# Fathom-Serial.net
KiCad netlist of a schematic drawn in EAGLE
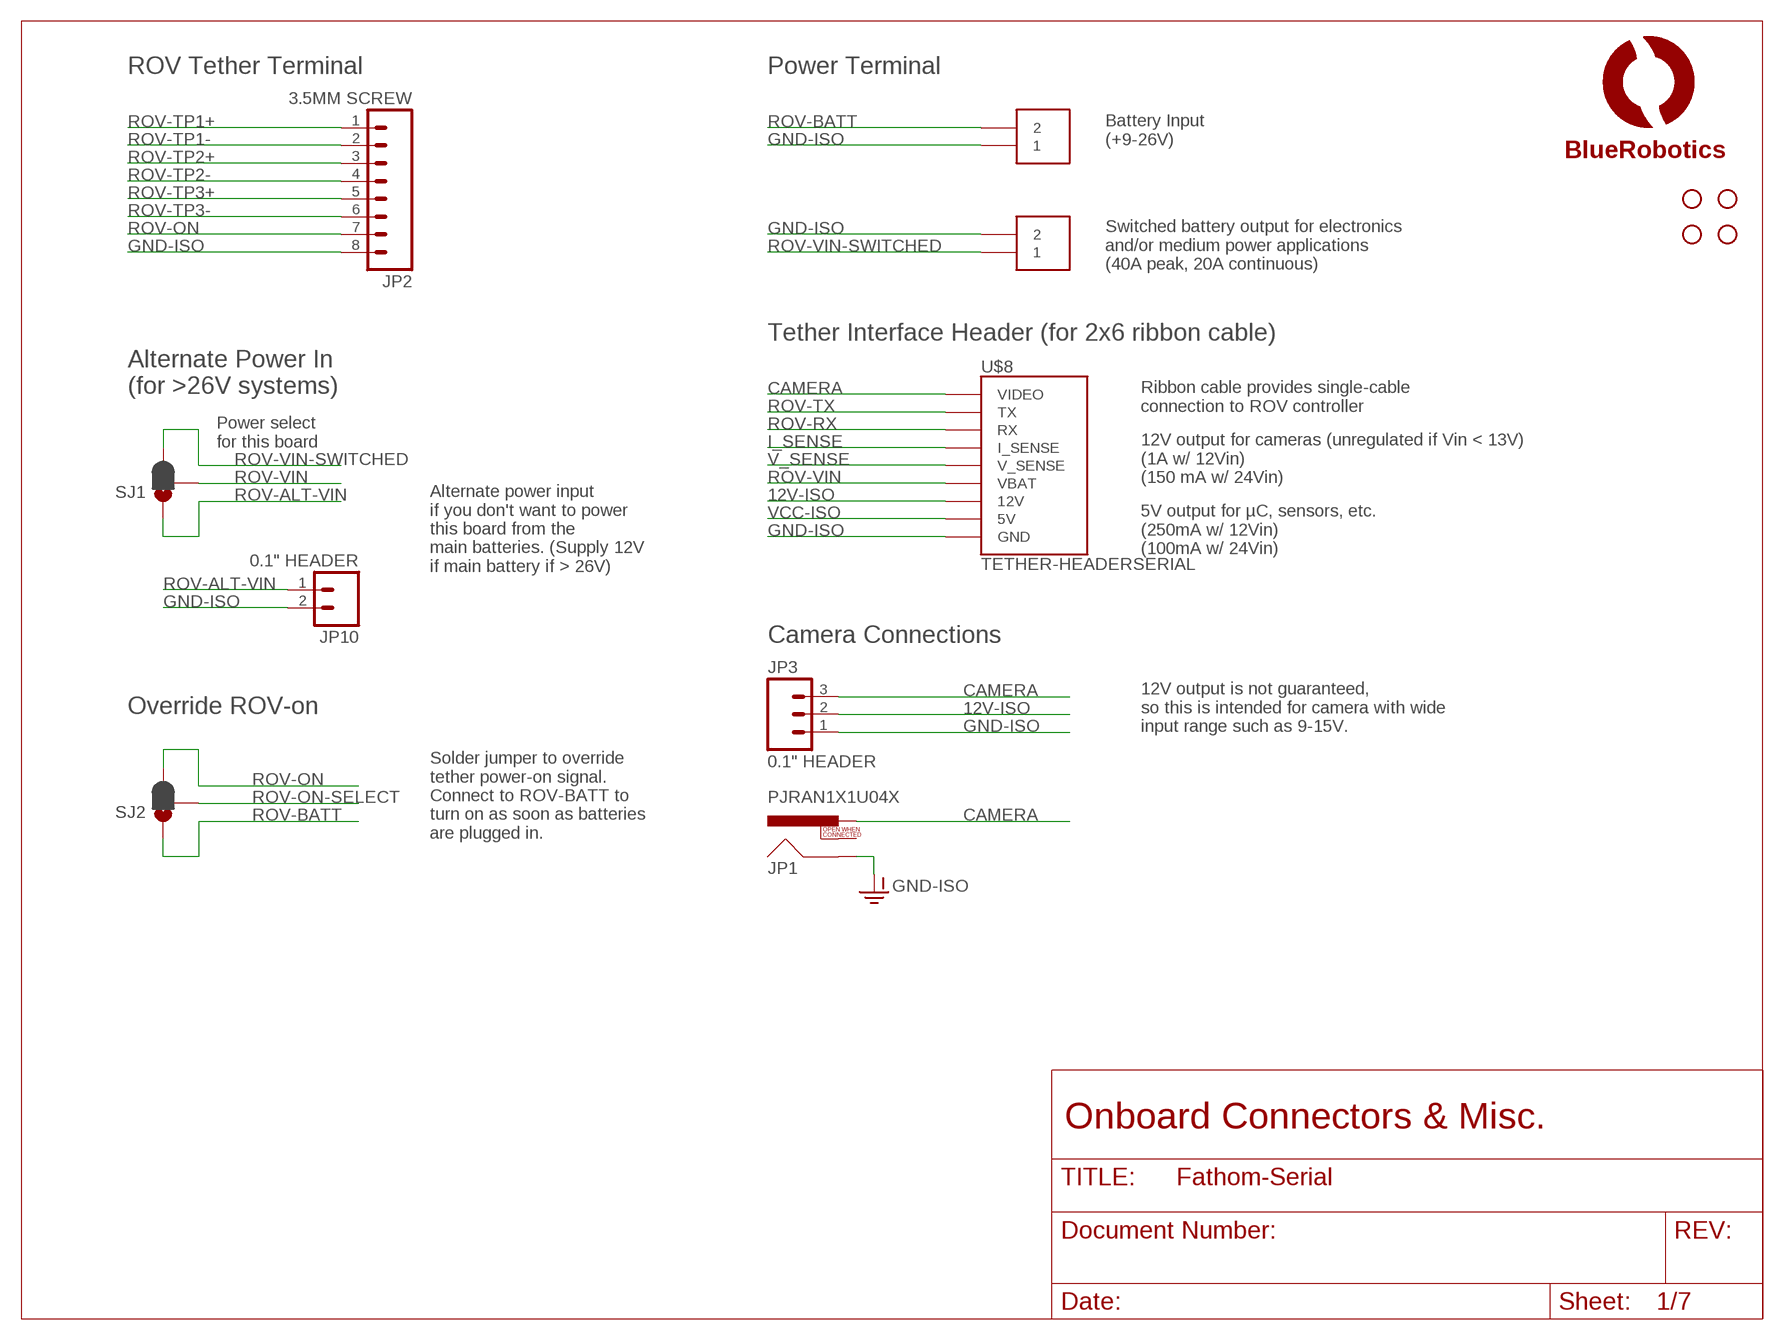
[diagram p0: schematic, sheet 1]
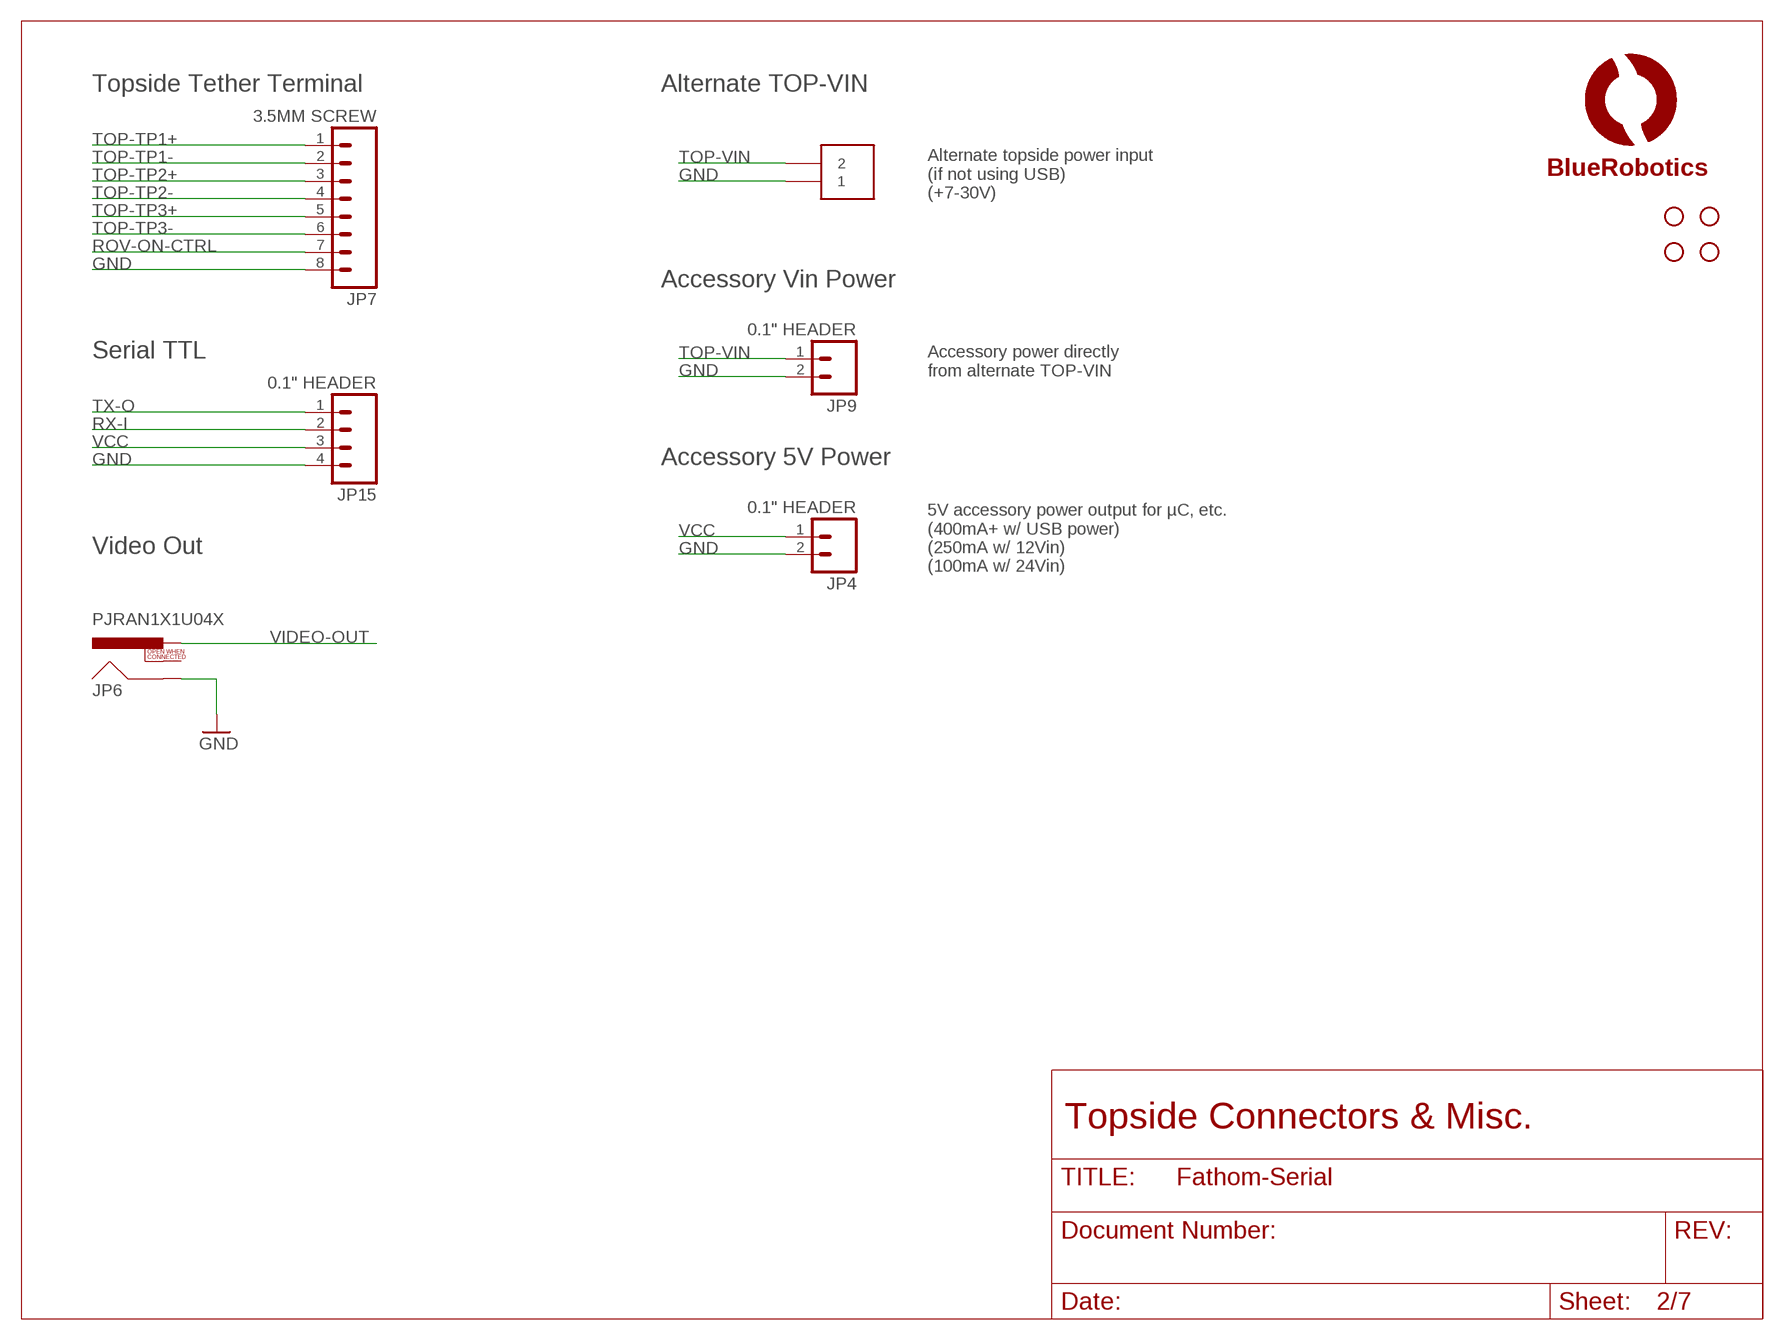
[diagram p1: schematic, sheet 2]
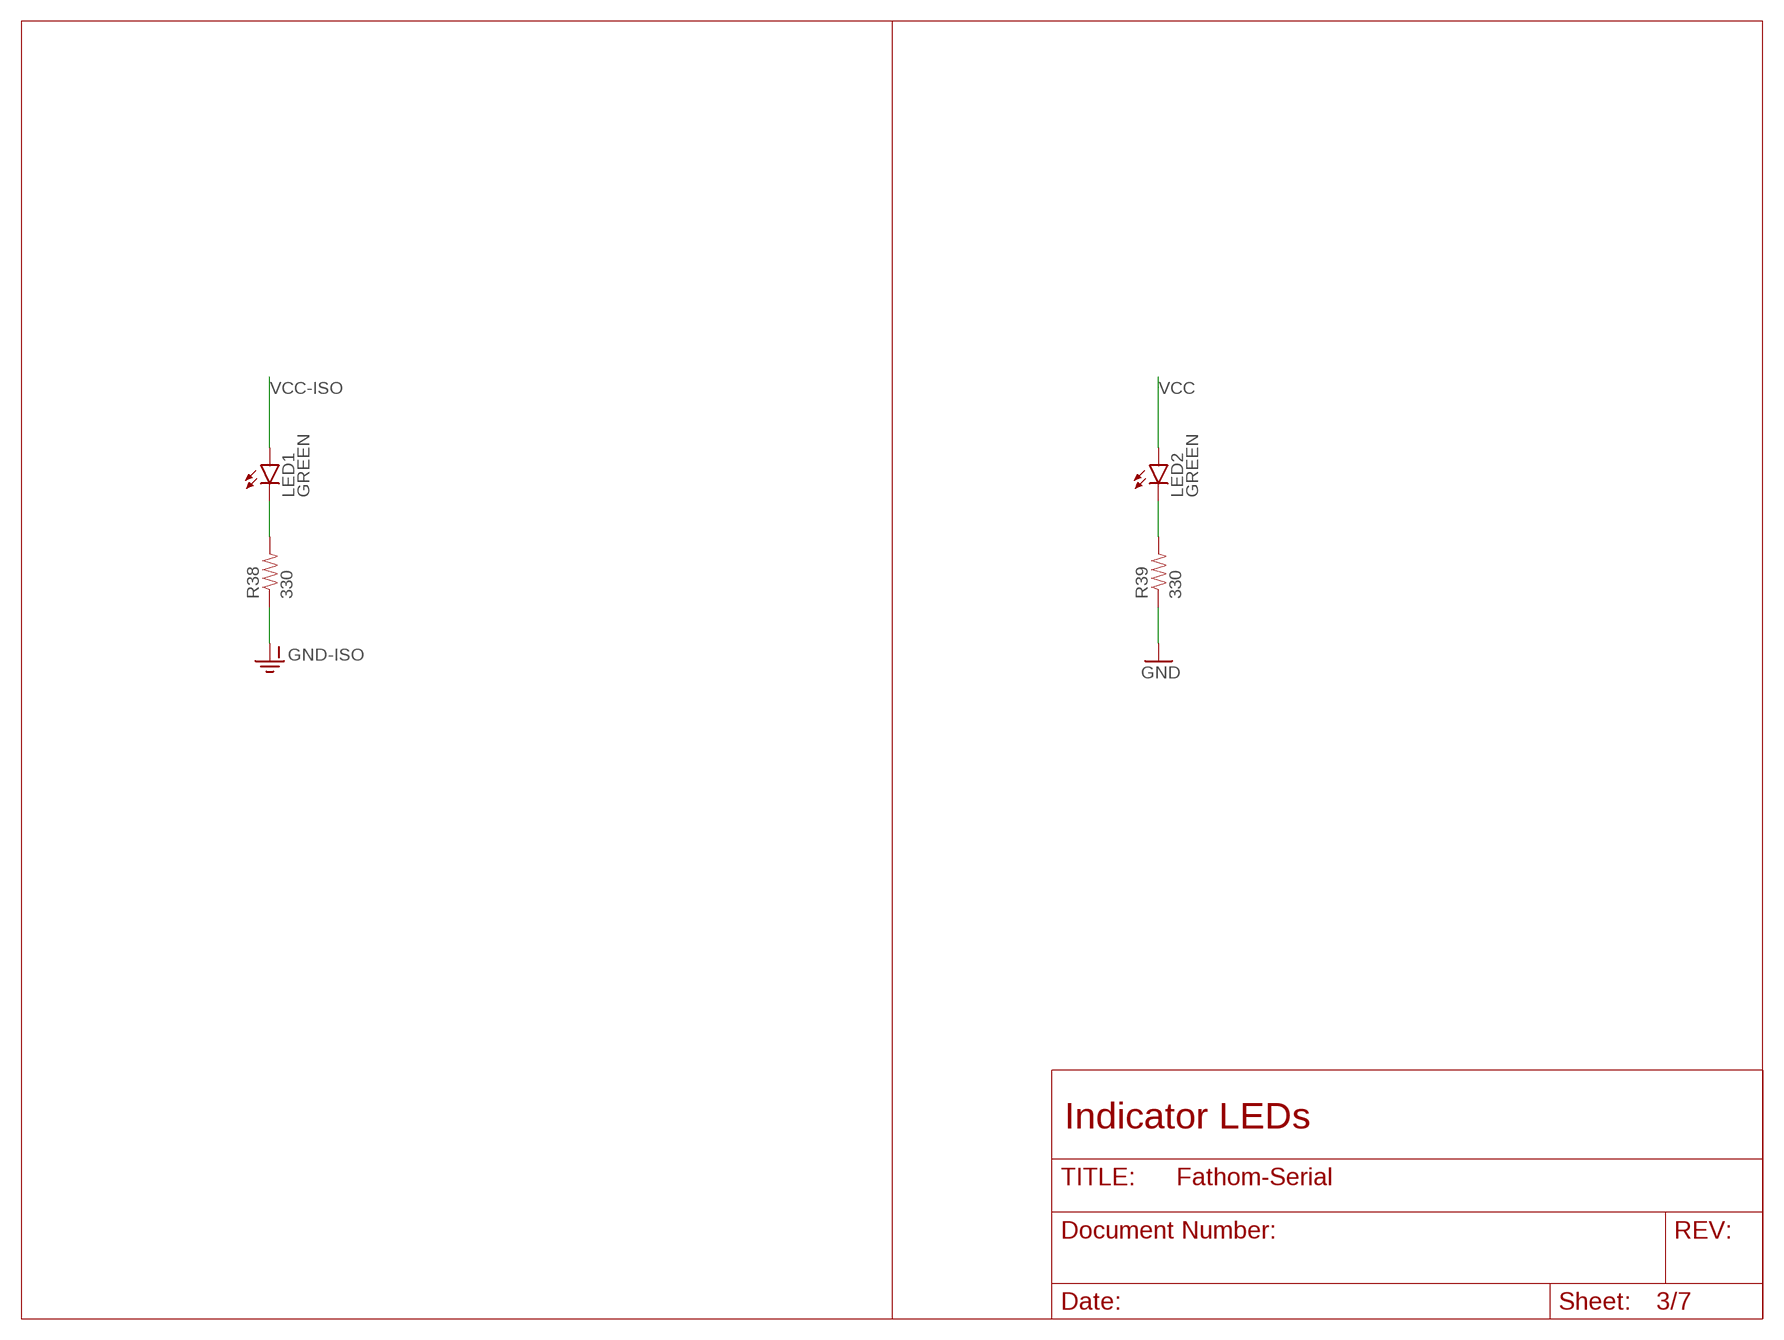
[diagram p2: schematic, sheet 3]
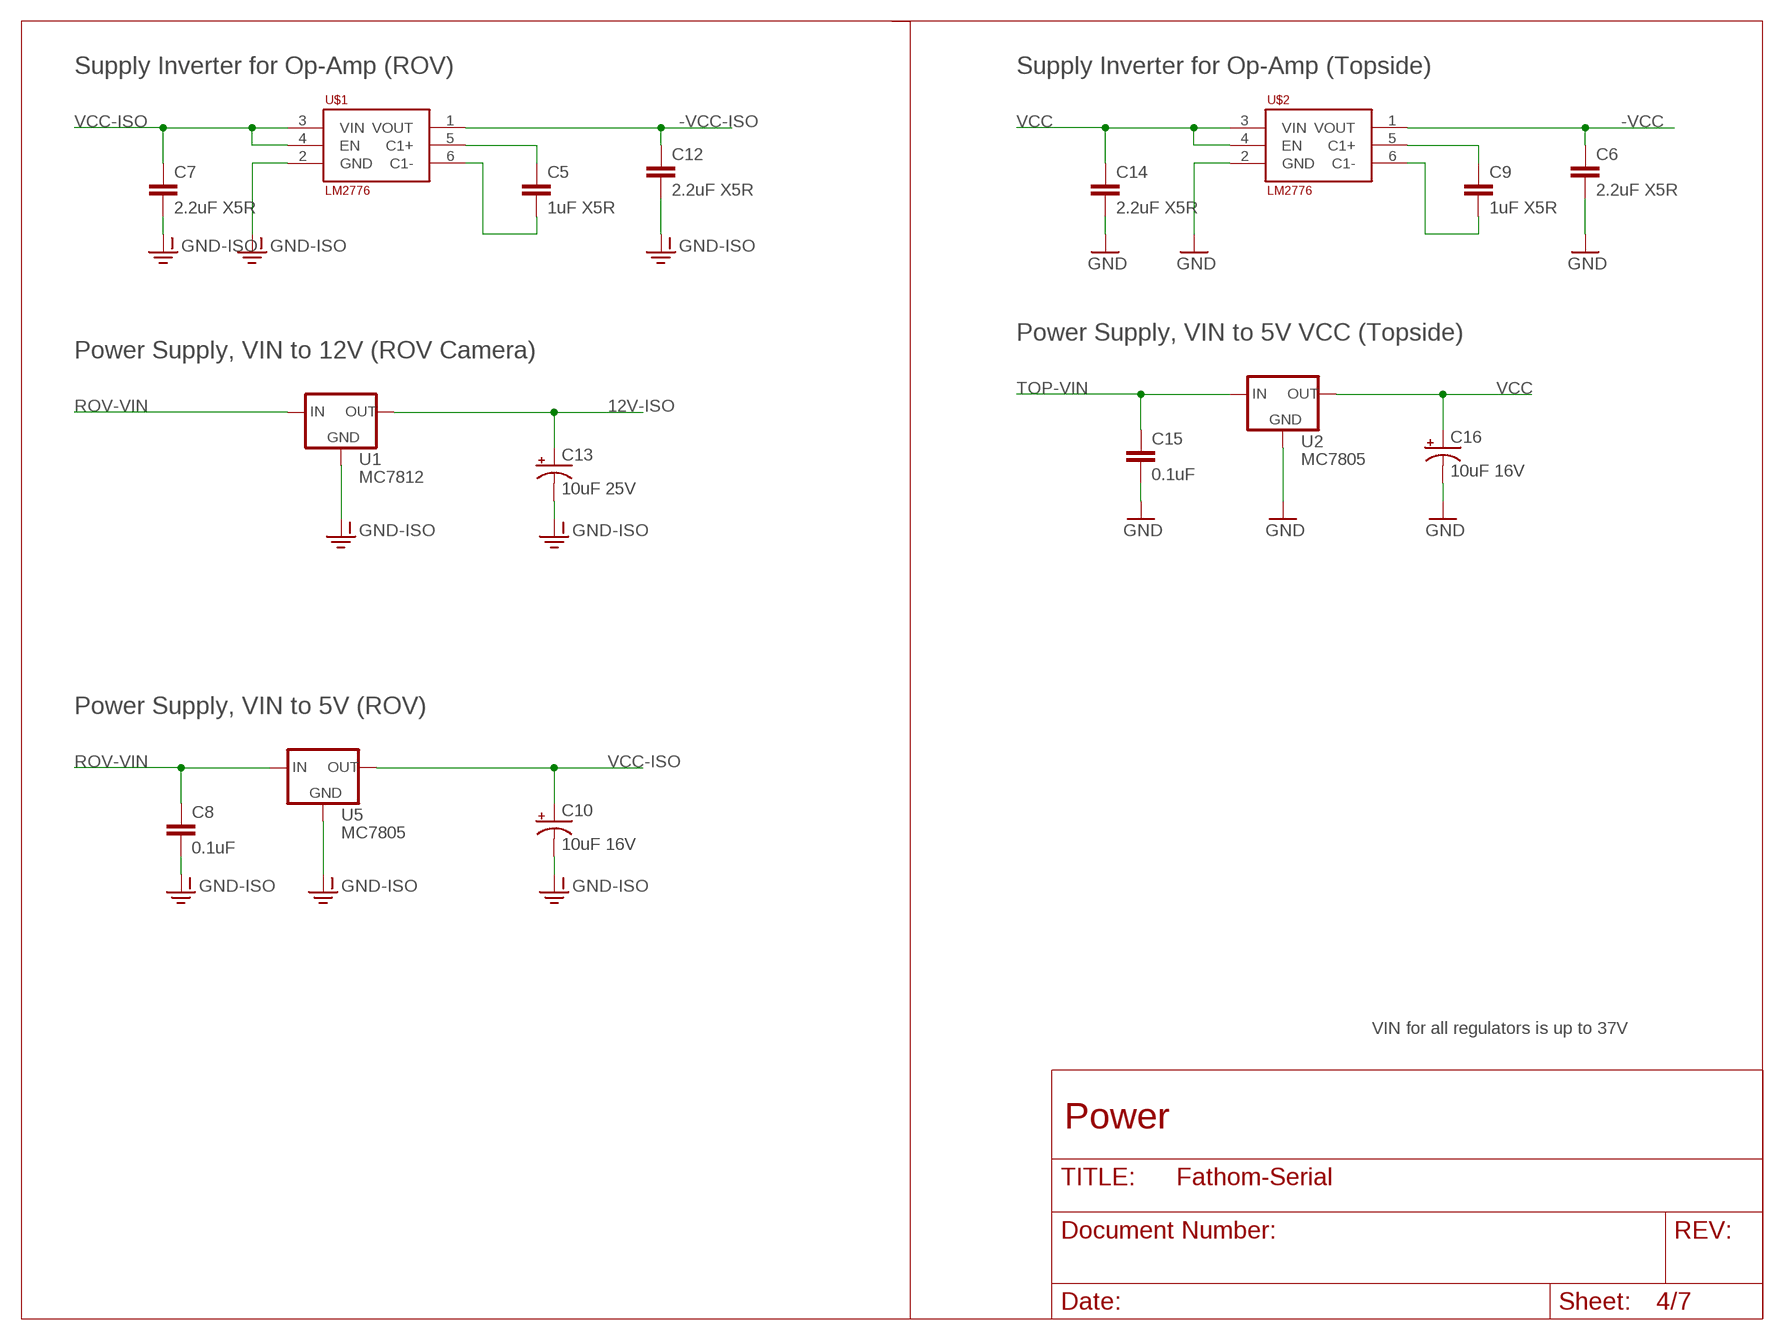
[diagram p3: schematic, sheet 4]
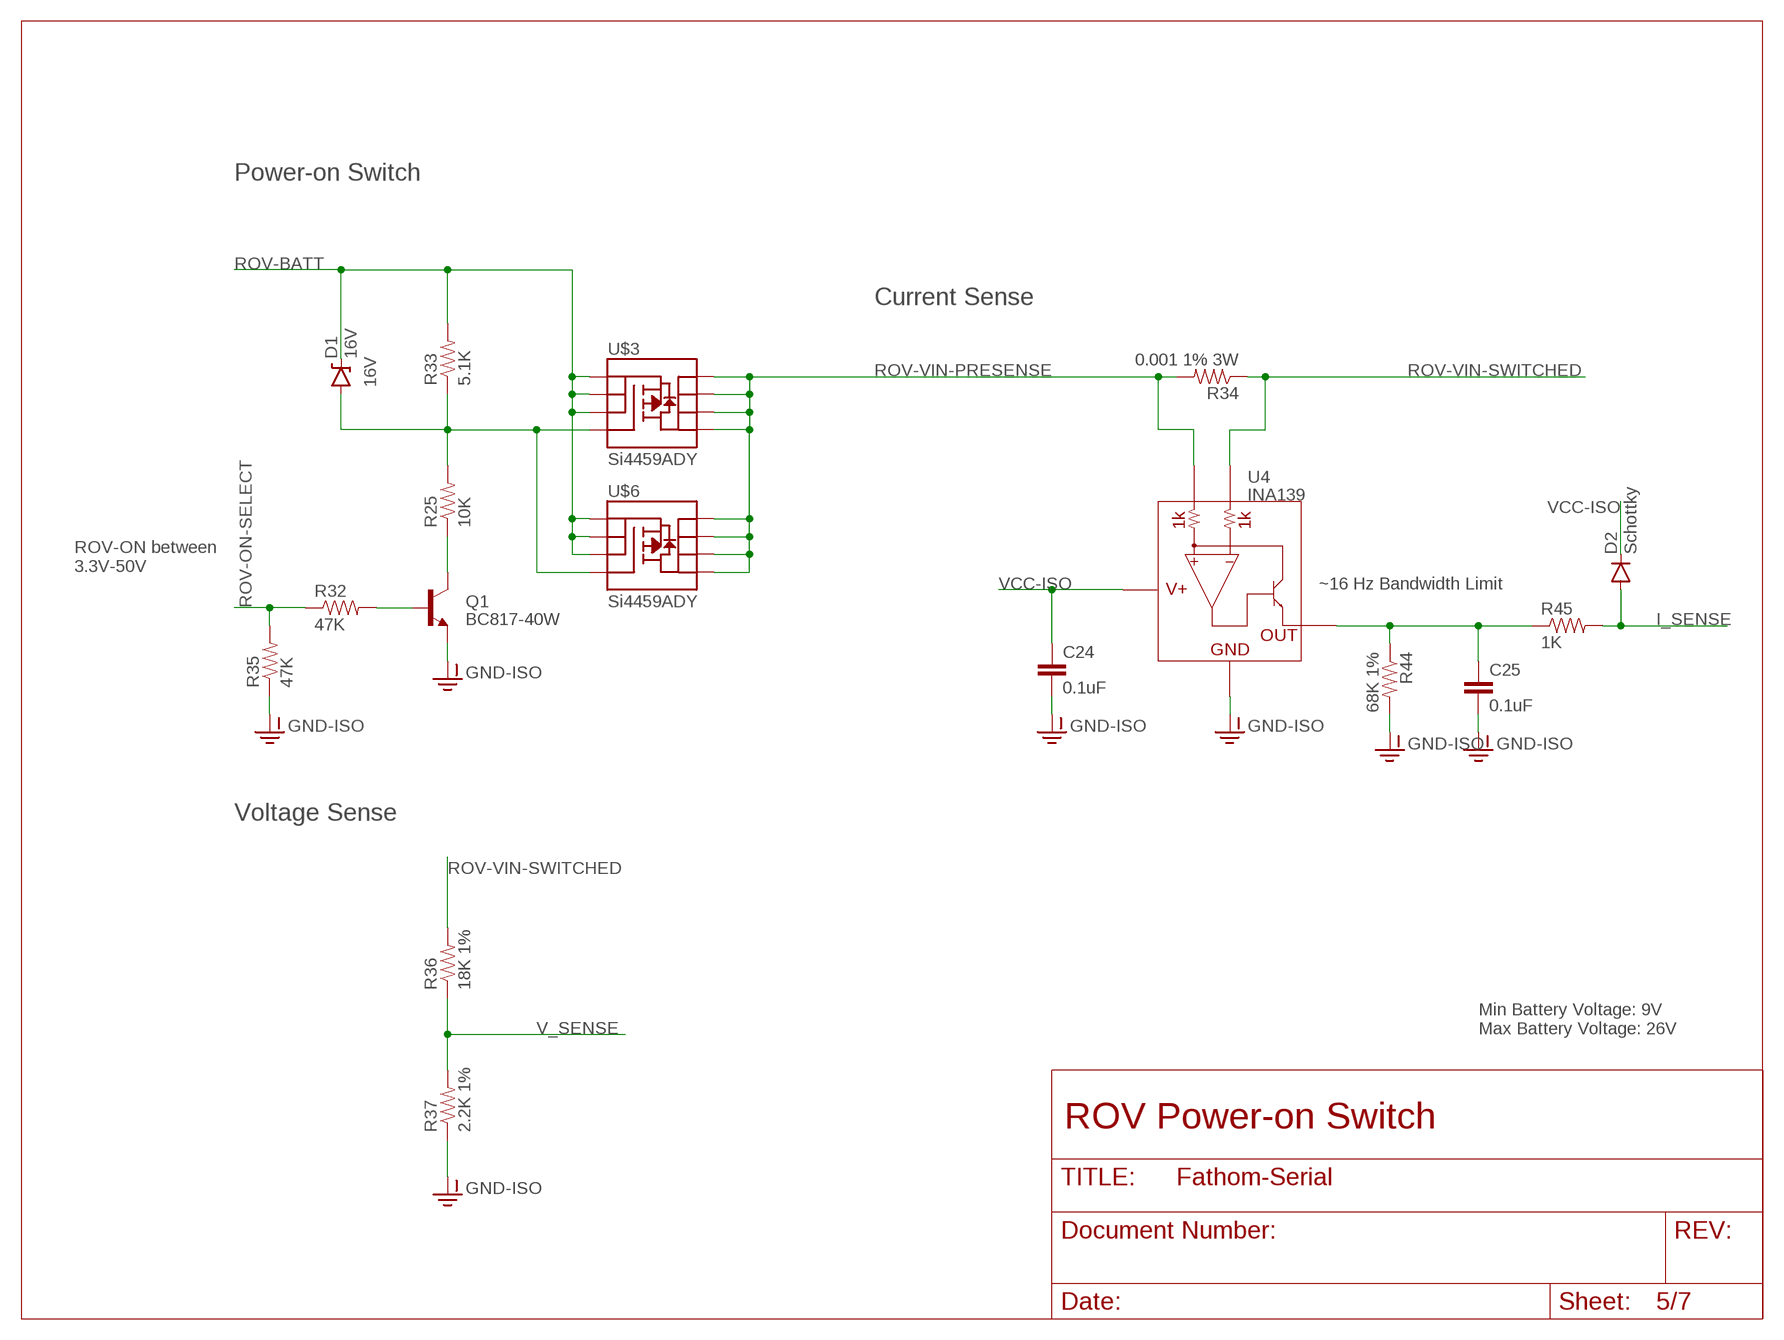
[diagram p4: schematic, sheet 5]
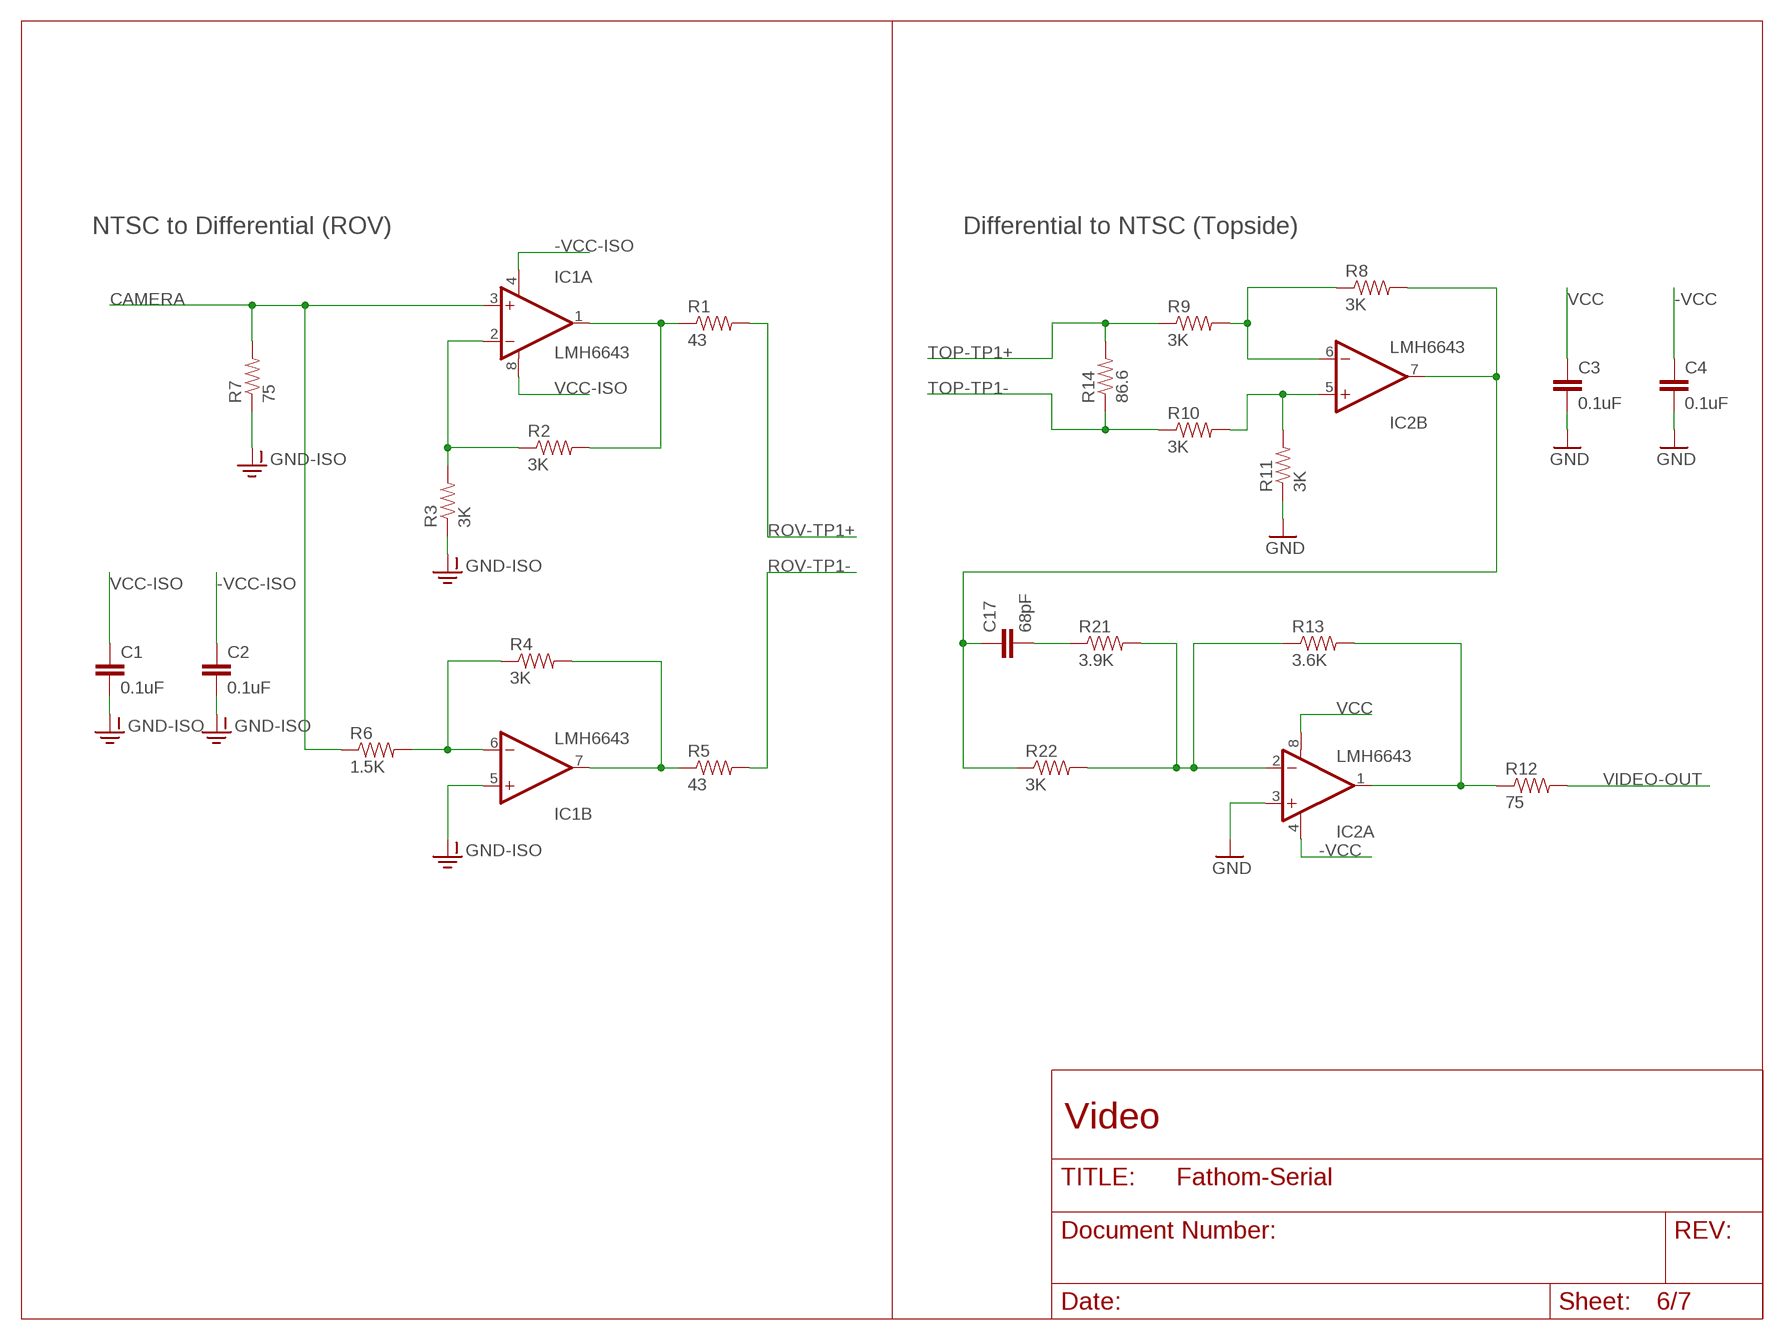
[diagram p5: schematic, sheet 6]
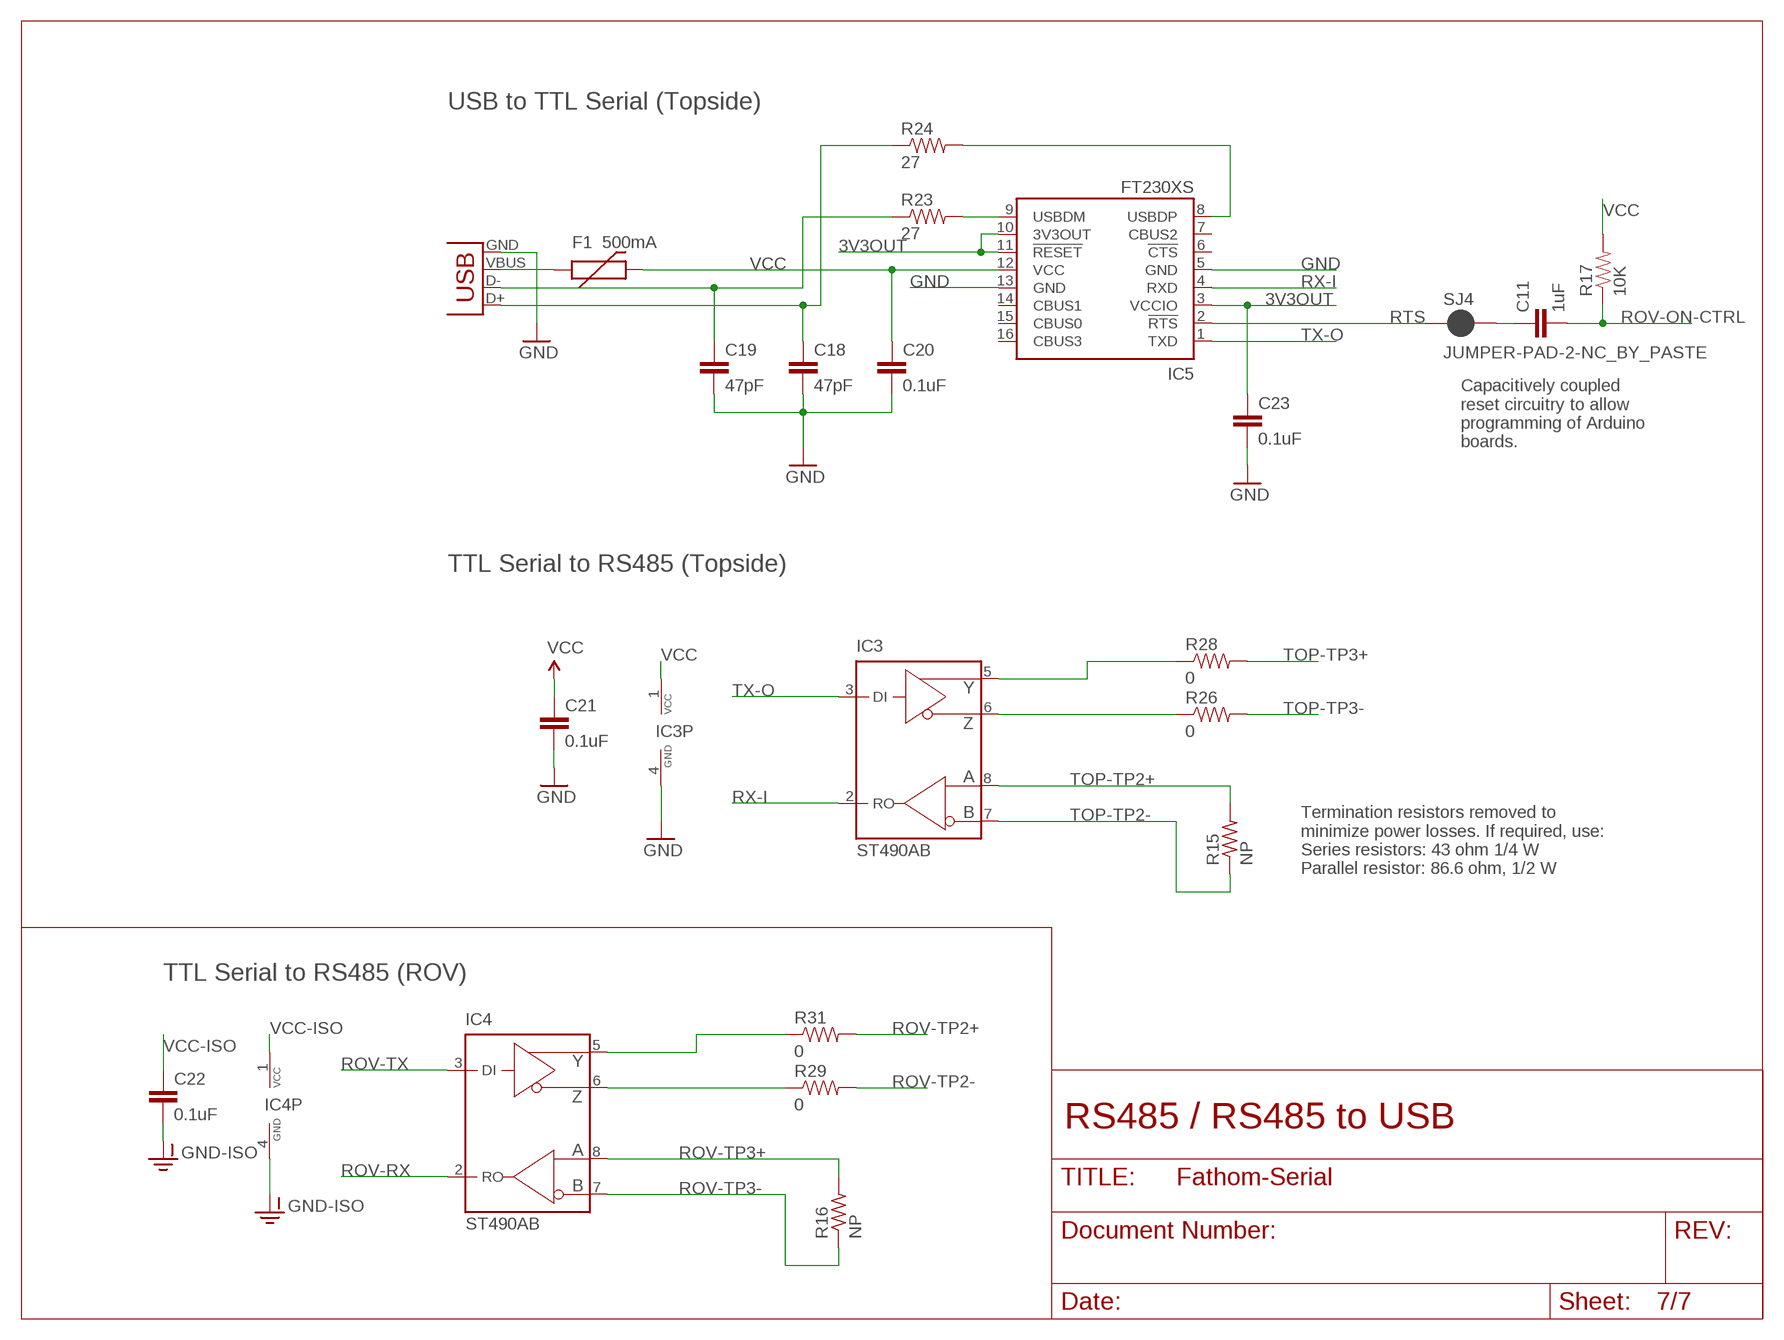
[diagram p6: schematic, sheet 7]

(export (version "E")
  (design (tool "Eeschema 10.0.6"))
  (components
    (comp (ref "JP1")
      (value "PJRAN1X1U04X")
      (footprint "eagle-import:RCA")
      (libsource (lib "eagle-import") (part "RCA"))
    )
    (comp (ref "JP2")
      (value "3.5MM SCREW")
      (footprint "eagle-import:SCREWTERMINAL-3.5MM-8")
      (libsource (lib "eagle-import") (part "M083.5MM-8"))
    )
    (comp (ref "JP3")
      (value "0.1\" HEADER")
      (footprint "eagle-import:1X03")
      (libsource (lib "eagle-import") (part "M03PTH"))
    )
    (comp (ref "JP10")
      (value "0.1\" HEADER")
      (footprint "eagle-import:1X02")
      (libsource (lib "eagle-import") (part "M02PTH"))
    )
    (comp (ref "SJ1")
      (value "JUMPER-PAD-3-2OF3_NC_BY_PASTE")
      (footprint "eagle-import:PAD-JUMPER-3-2OF3_NC_BY_PASTE_YES_SILK_FULL_BOX")
      (libsource (lib "eagle-import") (part "JUMPER-PAD-3-2OF3_NC_BY_PASTE"))
    )
    (comp (ref "SJ2")
      (value "JUMPER-PAD-3-2OF3_NC_BY_PASTE")
      (footprint "eagle-import:PAD-JUMPER-3-2OF3_NC_BY_PASTE_YES_SILK_FULL_BOX")
      (libsource (lib "eagle-import") (part "JUMPER-PAD-3-2OF3_NC_BY_PASTE"))
    )
    (comp (ref "STANDOFF1")
      (value "STAND-OFF")
      (footprint "eagle-import:STAND-OFF")
      (libsource (lib "eagle-import") (part "STAND-OFF"))
    )
    (comp (ref "STANDOFF2")
      (value "STAND-OFF")
      (footprint "eagle-import:STAND-OFF")
      (libsource (lib "eagle-import") (part "STAND-OFF"))
    )
    (comp (ref "STANDOFF3")
      (value "STAND-OFF")
      (footprint "eagle-import:STAND-OFF")
      (libsource (lib "eagle-import") (part "STAND-OFF"))
    )
    (comp (ref "STANDOFF4")
      (value "STAND-OFF")
      (footprint "eagle-import:STAND-OFF")
      (libsource (lib "eagle-import") (part "STAND-OFF"))
    )
    (comp (ref "U$4")
      (value "LOGOFULL-M")
      (footprint "eagle-import:BR-FULL-LOGO-MEDIUM")
      (libsource (lib "eagle-import") (part "LOGOFULL-M"))
    )
    (comp (ref "U$8")
      (value "TETHER-HEADERSERIAL")
      (footprint "eagle-import:TETHER-HEADER-2X7")
      (libsource (lib "eagle-import") (part "TETHER-HEADERSERIAL"))
    )
    (comp (ref "U$10")
      (value "HEADER-2")
      (footprint "eagle-import:TETHER-POWER-TERMINALS")
      (libsource (lib "eagle-import") (part "HEADER-2"))
    )
    (comp (ref "U$11")
      (value "HEADER-2")
      (footprint "eagle-import:TETHER-POWER-TERMINALS")
      (libsource (lib "eagle-import") (part "HEADER-2"))
    )
    (comp (ref "LED1")
      (value "GREEN")
      (footprint "eagle-import:LED-0603")
      (libsource (lib "eagle-import") (part "LED0603"))
    )
    (comp (ref "LED2")
      (value "GREEN")
      (footprint "eagle-import:LED-0603")
      (libsource (lib "eagle-import") (part "LED0603"))
    )
    (comp (ref "R38")
      (value "330")
      (footprint "eagle-import:0603-RES")
      (libsource (lib "eagle-import") (part "33KOHM1/10W1%(0603)"))
    )
    (comp (ref "R39")
      (value "330")
      (footprint "eagle-import:0603-RES")
      (libsource (lib "eagle-import") (part "33KOHM1/10W1%(0603)"))
    )
    (comp (ref "C11")
      (value "1uF")
      (footprint "eagle-import:0603-CAP")
      (libsource (lib "eagle-import") (part "CAP0603-CAP"))
    )
    (comp (ref "C18")
      (value "47pF")
      (footprint "eagle-import:0603-CAP")
      (libsource (lib "eagle-import") (part "CAP0603-CAP"))
    )
    (comp (ref "C19")
      (value "47pF")
      (footprint "eagle-import:0603-CAP")
      (libsource (lib "eagle-import") (part "CAP0603-CAP"))
    )
    (comp (ref "C20")
      (value "0.1uF")
      (footprint "eagle-import:0603-CAP")
      (libsource (lib "eagle-import") (part "CAP0603-CAP"))
    )
    (comp (ref "C21")
      (value "0.1uF")
      (footprint "eagle-import:0603-CAP")
      (libsource (lib "eagle-import") (part "CAP0603-CAP"))
    )
    (comp (ref "C22")
      (value "0.1uF")
      (footprint "eagle-import:0603-CAP")
      (libsource (lib "eagle-import") (part "CAP0603-CAP"))
    )
    (comp (ref "C23")
      (value "0.1uF")
      (footprint "eagle-import:0603-CAP")
      (libsource (lib "eagle-import") (part "CAP0603-CAP"))
    )
    (comp (ref "F1")
      (value "500mA")
      (footprint "eagle-import:0603")
      (libsource (lib "eagle-import") (part "PTC0603"))
    )
    (comp (ref "IC3")
      (value "ST490AB")
      (footprint "eagle-import:SO08")
      (fields (field (name "MF") "MAXIM") (field (name "MPN") "MAX488CSA"))
      (libsource (lib "eagle-import") (part "MAX488CSA"))
    )
    (comp (ref "IC4")
      (value "ST490AB")
      (footprint "eagle-import:SO08")
      (fields (field (name "MF") "MAXIM") (field (name "MPN") "MAX488CSA"))
      (libsource (lib "eagle-import") (part "MAX488CSA"))
    )
    (comp (ref "IC5")
      (value "FT230XS")
      (footprint "eagle-import:SSOP16")
      (libsource (lib "eagle-import") (part "FT230XS"))
    )
    (comp (ref "R15")
      (value "NP")
      (footprint "eagle-import:R1210")
      (libsource (lib "eagle-import") (part "R-US_R1210"))
    )
    (comp (ref "R16")
      (value "NP")
      (footprint "eagle-import:R1210")
      (libsource (lib "eagle-import") (part "R-US_R1210"))
    )
    (comp (ref "R17")
      (value "10K")
      (footprint "eagle-import:0603-RES")
      (libsource (lib "eagle-import") (part "RESISTOR0603-RES"))
    )
    (comp (ref "R23")
      (value "27")
      (footprint "eagle-import:0603-RES")
      (libsource (lib "eagle-import") (part "RESISTOR0603-RES"))
    )
    (comp (ref "R24")
      (value "27")
      (footprint "eagle-import:0603-RES")
      (libsource (lib "eagle-import") (part "RESISTOR0603-RES"))
    )
    (comp (ref "R26")
      (value "0")
      (footprint "eagle-import:1206")
      (libsource (lib "eagle-import") (part "RESISTOR1206"))
    )
    (comp (ref "R28")
      (value "0")
      (footprint "eagle-import:1206")
      (libsource (lib "eagle-import") (part "RESISTOR1206"))
    )
    (comp (ref "R29")
      (value "0")
      (footprint "eagle-import:1206")
      (libsource (lib "eagle-import") (part "RESISTOR1206"))
    )
    (comp (ref "R31")
      (value "0")
      (footprint "eagle-import:1206")
      (libsource (lib "eagle-import") (part "RESISTOR1206"))
    )
    (comp (ref "SJ4")
      (value "JUMPER-PAD-2-NC_BY_PASTE")
      (footprint "eagle-import:PAD-JUMPER-2-NC_BY_PASTE_YES_SILK")
      (libsource (lib "eagle-import") (part "JUMPER-PAD-2-NC_BY_PASTE"))
    )
    (comp (ref "X2")
      (value "USBSMD")
      (footprint "eagle-import:USB-MINIB")
      (libsource (lib "eagle-import") (part "USBSMD"))
    )
    (comp (ref "C24")
      (value "0.1uF")
      (footprint "eagle-import:0603-CAP")
      (libsource (lib "eagle-import") (part "SparkFun-Passives_CAP0603-CAP"))
    )
    (comp (ref "C25")
      (value "0.1uF")
      (footprint "eagle-import:0603-CAP")
      (libsource (lib "eagle-import") (part "SparkFun-Passives_CAP0603-CAP"))
    )
    (comp (ref "D1")
      (value "16V")
      (footprint "eagle-import:SOD-323")
      (libsource (lib "eagle-import") (part "DIODE-ZENER3.3V"))
    )
    (comp (ref "D2")
      (value "Schottky")
      (footprint "eagle-import:SOD-323")
      (libsource (lib "eagle-import") (part "DIODESOD"))
    )
    (comp (ref "Q1")
      (value "BC817-40W")
      (footprint "eagle-import:SOT23")
      (libsource (lib "eagle-import") (part "TRANSISTOR_NPNSOT23"))
    )
    (comp (ref "R25")
      (value "10K")
      (footprint "eagle-import:0603-RES")
      (libsource (lib "eagle-import") (part "33KOHM1/10W1%(0603)"))
    )
    (comp (ref "R32")
      (value "47K")
      (footprint "eagle-import:0603-RES")
      (libsource (lib "eagle-import") (part "33KOHM1/10W1%(0603)"))
    )
    (comp (ref "R33")
      (value "5.1K")
      (footprint "eagle-import:0603-RES")
      (libsource (lib "eagle-import") (part "33KOHM1/10W1%(0603)"))
    )
    (comp (ref "R34")
      (value "0.001 1% 3W")
      (footprint "eagle-import:R2512")
      (libsource (lib "eagle-import") (part "SparkFun-Resistors_RESISTOR2512"))
    )
    (comp (ref "R35")
      (value "47K")
      (footprint "eagle-import:0603-RES")
      (libsource (lib "eagle-import") (part "33KOHM1/10W1%(0603)"))
    )
    (comp (ref "R36")
      (value "18K 1%")
      (footprint "eagle-import:0603-RES")
      (libsource (lib "eagle-import") (part "33KOHM1/10W1%(0603)"))
    )
    (comp (ref "R37")
      (value "2.2K 1%")
      (footprint "eagle-import:0603-RES")
      (libsource (lib "eagle-import") (part "33KOHM1/10W1%(0603)"))
    )
    (comp (ref "R44")
      (value "68K 1%")
      (footprint "eagle-import:0603-RES")
      (libsource (lib "eagle-import") (part "33KOHM1/10W1%(0603)"))
    )
    (comp (ref "R45")
      (value "1K")
      (footprint "eagle-import:0603-RES")
      (libsource (lib "eagle-import") (part "33KOHM1/10W1%(0603)"))
    )
    (comp (ref "U$3")
      (value "Si4459ADY")
      (footprint "eagle-import:SO08")
      (libsource (lib "eagle-import") (part "MOSFET-PCHANNEL-SOIC8SOIC8"))
    )
    (comp (ref "U$6")
      (value "Si4459ADY")
      (footprint "eagle-import:SO08")
      (libsource (lib "eagle-import") (part "MOSFET-PCHANNEL-SOIC8SOIC8"))
    )
    (comp (ref "U4")
      (value "INA139")
      (footprint "eagle-import:SOT23-5")
      (libsource (lib "eagle-import") (part "INA139"))
    )
    (comp (ref "C5")
      (value "1uF X5R")
      (footprint "eagle-import:0603-CAP")
      (libsource (lib "eagle-import") (part "SparkFun-Passives_CAP0603-CAP"))
    )
    (comp (ref "C6")
      (value "2.2uF X5R")
      (footprint "eagle-import:0603-CAP")
      (libsource (lib "eagle-import") (part "SparkFun-Passives_CAP0603-CAP"))
    )
    (comp (ref "C7")
      (value "2.2uF X5R")
      (footprint "eagle-import:0603-CAP")
      (libsource (lib "eagle-import") (part "SparkFun-Passives_CAP0603-CAP"))
    )
    (comp (ref "C8")
      (value "0.1uF")
      (footprint "eagle-import:0603-CAP")
      (libsource (lib "eagle-import") (part "SparkFun-Passives_CAP0603-CAP"))
    )
    (comp (ref "C9")
      (value "1uF X5R")
      (footprint "eagle-import:0603-CAP")
      (libsource (lib "eagle-import") (part "SparkFun-Passives_CAP0603-CAP"))
    )
    (comp (ref "C10")
      (value "10uF 16V")
      (footprint "eagle-import:EIA3216")
      (libsource (lib "eagle-import") (part "CAP_POL1206"))
    )
    (comp (ref "C12")
      (value "2.2uF X5R")
      (footprint "eagle-import:0603-CAP")
      (libsource (lib "eagle-import") (part "SparkFun-Passives_CAP0603-CAP"))
    )
    (comp (ref "C13")
      (value "10uF 25V")
      (footprint "eagle-import:EIA6032")
      (libsource (lib "eagle-import") (part "CAP_POL6032"))
    )
    (comp (ref "C14")
      (value "2.2uF X5R")
      (footprint "eagle-import:0603-CAP")
      (libsource (lib "eagle-import") (part "SparkFun-Passives_CAP0603-CAP"))
    )
    (comp (ref "C15")
      (value "0.1uF")
      (footprint "eagle-import:0603-CAP")
      (libsource (lib "eagle-import") (part "SparkFun-Passives_CAP0603-CAP"))
    )
    (comp (ref "C16")
      (value "10uF 16V")
      (footprint "eagle-import:EIA3216")
      (libsource (lib "eagle-import") (part "CAP_POL1206"))
    )
    (comp (ref "U$1")
      (value "LM2776")
      (footprint "eagle-import:SOT-23-6")
      (libsource (lib "eagle-import") (part "LM2776"))
    )
    (comp (ref "U$2")
      (value "LM2776")
      (footprint "eagle-import:SOT-23-6")
      (libsource (lib "eagle-import") (part "LM2776"))
    )
    (comp (ref "U1")
      (value "MC7812")
      (footprint "eagle-import:DPAK")
      (libsource (lib "eagle-import") (part "78XX"))
    )
    (comp (ref "U2")
      (value "MC7805")
      (footprint "eagle-import:DPAK")
      (libsource (lib "eagle-import") (part "78XX"))
    )
    (comp (ref "U5")
      (value "MC7805")
      (footprint "eagle-import:DPAK")
      (libsource (lib "eagle-import") (part "78XX"))
    )
    (comp (ref "JP4")
      (value "0.1\" HEADER")
      (footprint "eagle-import:1X02")
      (libsource (lib "eagle-import") (part "M02PTH"))
    )
    (comp (ref "JP6")
      (value "PJRAN1X1U04X")
      (footprint "eagle-import:RCA")
      (libsource (lib "eagle-import") (part "RCA"))
    )
    (comp (ref "JP7")
      (value "3.5MM SCREW")
      (footprint "eagle-import:SCREWTERMINAL-3.5MM-8")
      (libsource (lib "eagle-import") (part "M083.5MM-8"))
    )
    (comp (ref "JP9")
      (value "0.1\" HEADER")
      (footprint "eagle-import:1X02")
      (libsource (lib "eagle-import") (part "M02PTH"))
    )
    (comp (ref "JP15")
      (value "0.1\" HEADER")
      (footprint "eagle-import:1X04")
      (libsource (lib "eagle-import") (part "M04PTH"))
    )
    (comp (ref "STANDOFF5")
      (value "STAND-OFF")
      (footprint "eagle-import:STAND-OFF")
      (libsource (lib "eagle-import") (part "STAND-OFF"))
    )
    (comp (ref "STANDOFF6")
      (value "STAND-OFF")
      (footprint "eagle-import:STAND-OFF")
      (libsource (lib "eagle-import") (part "STAND-OFF"))
    )
    (comp (ref "STANDOFF7")
      (value "STAND-OFF")
      (footprint "eagle-import:STAND-OFF")
      (libsource (lib "eagle-import") (part "STAND-OFF"))
    )
    (comp (ref "STANDOFF8")
      (value "STAND-OFF")
      (footprint "eagle-import:STAND-OFF")
      (libsource (lib "eagle-import") (part "STAND-OFF"))
    )
    (comp (ref "U$5")
      (value "LOGOBR-LOGO-MS")
      (footprint "eagle-import:BR-LOGO-MEDIUM-SMALL")
      (libsource (lib "eagle-import") (part "LOGOBR-LOGO-MS"))
    )
    (comp (ref "U$12")
      (value "HEADER-2")
      (footprint "eagle-import:TETHER-POWER-TERMINALS")
      (libsource (lib "eagle-import") (part "HEADER-2"))
    )
    (comp (ref "C1")
      (value "0.1uF")
      (footprint "eagle-import:0603-CAP")
      (libsource (lib "eagle-import") (part "SparkFun-Passives_CAP0603-CAP"))
    )
    (comp (ref "C2")
      (value "0.1uF")
      (footprint "eagle-import:0603-CAP")
      (libsource (lib "eagle-import") (part "SparkFun-Passives_CAP0603-CAP"))
    )
    (comp (ref "C3")
      (value "0.1uF")
      (footprint "eagle-import:0603-CAP")
      (libsource (lib "eagle-import") (part "SparkFun-Passives_CAP0603-CAP"))
    )
    (comp (ref "C4")
      (value "0.1uF")
      (footprint "eagle-import:0603-CAP")
      (libsource (lib "eagle-import") (part "SparkFun-Passives_CAP0603-CAP"))
    )
    (comp (ref "C17")
      (value "68pF")
      (footprint "eagle-import:0603-CAP")
      (libsource (lib "eagle-import") (part "SparkFun-Passives_CAP0603-CAP"))
    )
    (comp (ref "IC1")
      (value "LMH6643")
      (footprint "eagle-import:SO08")
      (libsource (lib "eagle-import") (part "OPAMP-DUALU"))
    )
    (comp (ref "IC2")
      (value "LMH6643")
      (footprint "eagle-import:SO08")
      (libsource (lib "eagle-import") (part "OPAMP-DUALU"))
    )
    (comp (ref "R1")
      (value "43")
      (footprint "eagle-import:0603-RES")
      (libsource (lib "eagle-import") (part "SparkFun-Passives_RESISTOR0603-RES"))
    )
    (comp (ref "R2")
      (value "3K")
      (footprint "eagle-import:0603-RES")
      (libsource (lib "eagle-import") (part "SparkFun-Passives_RESISTOR0603-RES"))
    )
    (comp (ref "R3")
      (value "3K")
      (footprint "eagle-import:0603-RES")
      (libsource (lib "eagle-import") (part "SparkFun-Passives_RESISTOR0603-RES"))
    )
    (comp (ref "R4")
      (value "3K")
      (footprint "eagle-import:0603-RES")
      (libsource (lib "eagle-import") (part "SparkFun-Passives_RESISTOR0603-RES"))
    )
    (comp (ref "R5")
      (value "43")
      (footprint "eagle-import:0603-RES")
      (libsource (lib "eagle-import") (part "SparkFun-Passives_RESISTOR0603-RES"))
    )
    (comp (ref "R6")
      (value "1.5K")
      (footprint "eagle-import:0603-RES")
      (libsource (lib "eagle-import") (part "SparkFun-Passives_RESISTOR0603-RES"))
    )
    (comp (ref "R7")
      (value "75")
      (footprint "eagle-import:0603-RES")
      (libsource (lib "eagle-import") (part "SparkFun-Passives_RESISTOR0603-RES"))
    )
    (comp (ref "R8")
      (value "3K")
      (footprint "eagle-import:0603-RES")
      (libsource (lib "eagle-import") (part "SparkFun-Passives_RESISTOR0603-RES"))
    )
    (comp (ref "R9")
      (value "3K")
      (footprint "eagle-import:0603-RES")
      (libsource (lib "eagle-import") (part "SparkFun-Passives_RESISTOR0603-RES"))
    )
    (comp (ref "R10")
      (value "3K")
      (footprint "eagle-import:0603-RES")
      (libsource (lib "eagle-import") (part "SparkFun-Passives_RESISTOR0603-RES"))
    )
    (comp (ref "R11")
      (value "3K")
      (footprint "eagle-import:0603-RES")
      (libsource (lib "eagle-import") (part "SparkFun-Passives_RESISTOR0603-RES"))
    )
    (comp (ref "R12")
      (value "75")
      (footprint "eagle-import:0603-RES")
      (libsource (lib "eagle-import") (part "SparkFun-Passives_RESISTOR0603-RES"))
    )
    (comp (ref "R13")
      (value "3.6K")
      (footprint "eagle-import:0603-RES")
      (libsource (lib "eagle-import") (part "SparkFun-Passives_RESISTOR0603-RES"))
    )
    (comp (ref "R14")
      (value "86.6")
      (footprint "eagle-import:0603-RES")
      (libsource (lib "eagle-import") (part "SparkFun-Passives_RESISTOR0603-RES"))
    )
    (comp (ref "R21")
      (value "3.9K")
      (footprint "eagle-import:0603-RES")
      (libsource (lib "eagle-import") (part "SparkFun-Passives_RESISTOR0603-RES"))
    )
    (comp (ref "R22")
      (value "3K")
      (footprint "eagle-import:0603-RES")
      (libsource (lib "eagle-import") (part "SparkFun-Passives_RESISTOR0603-RES"))
    )
  )
  (nets
    (net (code "1") (name "-VCC") (class "Default")
      (node (ref "C4") (pin "1") (pinfunction "1_1") (pintype "passive"))
      (node (ref "C6") (pin "1") (pinfunction "1_1") (pintype "passive"))
      (node (ref "IC2") (pin "4") (pinfunction "V-_4") (pintype "power_in"))
      (node (ref "U$2") (pin "1") (pinfunction "VOUT_1") (pintype "bidirectional"))
    )
    (net (code "2") (name "-VCC-ISO") (class "Default")
      (node (ref "C12") (pin "1") (pinfunction "1_1") (pintype "passive"))
      (node (ref "C2") (pin "1") (pinfunction "1_1") (pintype "passive"))
      (node (ref "IC1") (pin "4") (pinfunction "V-_4") (pintype "power_in"))
      (node (ref "U$1") (pin "1") (pinfunction "VOUT_1") (pintype "bidirectional"))
    )
    (net (code "3") (name "3V3OUT") (class "Default")
      (node (ref "C23") (pin "1") (pinfunction "1_1") (pintype "passive"))
      (node (ref "IC5") (pin "10") (pinfunction "3V3OUT_10") (pintype "output"))
      (node (ref "IC5") (pin "11") (pinfunction "~{RESET}_11") (pintype "input"))
      (node (ref "IC5") (pin "3") (pinfunction "VCCIO_3") (pintype "power_in"))
    )
    (net (code "4") (name "12V-ISO") (class "Default")
      (node (ref "C13") (pin "P$1") (pinfunction "+_P$1") (pintype "passive"))
      (node (ref "JP3") (pin "2") (pinfunction "2_2") (pintype "passive"))
      (node (ref "U$8") (pin "12V") (pinfunction "12V_12V") (pintype "bidirectional"))
      (node (ref "U1") (pin "3") (pinfunction "OUT_3") (pintype "output"))
    )
    (net (code "5") (name "CAMERA") (class "Default")
      (node (ref "IC1") (pin "3") (pinfunction "+IN_3") (pintype "input"))
      (node (ref "JP1") (pin "PIN") (pinfunction "PIN_PIN") (pintype "bidirectional"))
      (node (ref "JP3") (pin "3") (pinfunction "3_3") (pintype "passive"))
      (node (ref "R6") (pin "1") (pinfunction "1_1") (pintype "passive"))
      (node (ref "R7") (pin "2") (pinfunction "2_2") (pintype "passive"))
      (node (ref "U$8") (pin "VIDEO") (pinfunction "VIDEO_VIDEO") (pintype "bidirectional"))
    )
    (net (code "6") (name "GND") (class "Default")
      (node (ref "C14") (pin "2") (pinfunction "2_2") (pintype "passive"))
      (node (ref "C15") (pin "2") (pinfunction "2_2") (pintype "passive"))
      (node (ref "C16") (pin "C") (pinfunction "-_C") (pintype "passive"))
      (node (ref "C18") (pin "2") (pinfunction "2_2") (pintype "passive"))
      (node (ref "C19") (pin "2") (pinfunction "2_2") (pintype "passive"))
      (node (ref "C20") (pin "2") (pinfunction "2_2") (pintype "passive"))
      (node (ref "C21") (pin "2") (pinfunction "2_2") (pintype "passive"))
      (node (ref "C23") (pin "2") (pinfunction "2_2") (pintype "passive"))
      (node (ref "C3") (pin "2") (pinfunction "2_2") (pintype "passive"))
      (node (ref "C4") (pin "2") (pinfunction "2_2") (pintype "passive"))
      (node (ref "C6") (pin "2") (pinfunction "2_2") (pintype "passive"))
      (node (ref "IC2") (pin "3") (pinfunction "+IN_3") (pintype "input"))
      (node (ref "IC3") (pin "4") (pinfunction "GND_4") (pintype "power_in"))
      (node (ref "IC5") (pin "13") (pinfunction "GND_13") (pintype "power_in"))
      (node (ref "IC5") (pin "5") (pinfunction "GND_5") (pintype "power_in"))
      (node (ref "JP15") (pin "4") (pinfunction "4_4") (pintype "passive"))
      (node (ref "JP4") (pin "2") (pinfunction "2_2") (pintype "passive"))
      (node (ref "JP6") (pin "SHELL") (pinfunction "SHELL_SHELL") (pintype "bidirectional"))
      (node (ref "JP7") (pin "8") (pinfunction "8_8") (pintype "passive"))
      (node (ref "JP9") (pin "2") (pinfunction "2_2") (pintype "passive"))
      (node (ref "R11") (pin "1") (pinfunction "1_1") (pintype "passive"))
      (node (ref "R39") (pin "1") (pinfunction "1_1") (pintype "passive"))
      (node (ref "U$12") (pin "1A") (pinfunction "1_1A") (pintype "bidirectional"))
      (node (ref "U$12") (pin "1B") (pinfunction "1_1B") (pintype "bidirectional"))
      (node (ref "U$2") (pin "2") (pinfunction "GND_2") (pintype "bidirectional"))
      (node (ref "U2") (pin "4") (pinfunction "GND_4") (pintype "input"))
      (node (ref "X2") (pin "GND") (pinfunction "GND_GND") (pintype "bidirectional"))
    )
    (net (code "7") (name "GND-ISO") (class "Default")
      (node (ref "C1") (pin "2") (pinfunction "2_2") (pintype "passive"))
      (node (ref "C10") (pin "C") (pinfunction "-_C") (pintype "passive"))
      (node (ref "C12") (pin "2") (pinfunction "2_2") (pintype "passive"))
      (node (ref "C13") (pin "P$2") (pinfunction "-_P$2") (pintype "passive"))
      (node (ref "C2") (pin "2") (pinfunction "2_2") (pintype "passive"))
      (node (ref "C22") (pin "2") (pinfunction "2_2") (pintype "passive"))
      (node (ref "C24") (pin "2") (pinfunction "2_2") (pintype "passive"))
      (node (ref "C25") (pin "2") (pinfunction "2_2") (pintype "passive"))
      (node (ref "C7") (pin "2") (pinfunction "2_2") (pintype "passive"))
      (node (ref "C8") (pin "2") (pinfunction "2_2") (pintype "passive"))
      (node (ref "IC1") (pin "5") (pinfunction "+IN_5") (pintype "input"))
      (node (ref "IC4") (pin "4") (pinfunction "GND_4") (pintype "power_in"))
      (node (ref "JP1") (pin "SHELL") (pinfunction "SHELL_SHELL") (pintype "bidirectional"))
      (node (ref "JP10") (pin "2") (pinfunction "2_2") (pintype "passive"))
      (node (ref "JP2") (pin "8") (pinfunction "8_8") (pintype "passive"))
      (node (ref "JP3") (pin "1") (pinfunction "1_1") (pintype "passive"))
      (node (ref "Q1") (pin "2") (pinfunction "E_2") (pintype "passive"))
      (node (ref "R3") (pin "1") (pinfunction "1_1") (pintype "passive"))
      (node (ref "R35") (pin "1") (pinfunction "1_1") (pintype "passive"))
      (node (ref "R37") (pin "1") (pinfunction "1_1") (pintype "passive"))
      (node (ref "R38") (pin "1") (pinfunction "1_1") (pintype "passive"))
      (node (ref "R44") (pin "2") (pinfunction "2_2") (pintype "passive"))
      (node (ref "R7") (pin "1") (pinfunction "1_1") (pintype "passive"))
      (node (ref "U$1") (pin "2") (pinfunction "GND_2") (pintype "bidirectional"))
      (node (ref "U$10") (pin "1A") (pinfunction "1_1A") (pintype "bidirectional"))
      (node (ref "U$10") (pin "1B") (pinfunction "1_1B") (pintype "bidirectional"))
      (node (ref "U$11") (pin "2A") (pinfunction "2_2A") (pintype "bidirectional"))
      (node (ref "U$11") (pin "2B") (pinfunction "2_2B") (pintype "bidirectional"))
      (node (ref "U$8") (pin "GND0") (pinfunction "GND_GND0") (pintype "bidirectional"))
      (node (ref "U$8") (pin "GND1") (pinfunction "GND_GND1") (pintype "bidirectional"))
      (node (ref "U$8") (pin "GND2") (pinfunction "GND_GND2") (pintype "bidirectional"))
      (node (ref "U1") (pin "4") (pinfunction "GND_4") (pintype "input"))
      (node (ref "U4") (pin "2") (pinfunction "GND_2") (pintype "bidirectional"))
      (node (ref "U5") (pin "4") (pinfunction "GND_4") (pintype "input"))
    )
    (net (code "8") (name "I_SENSE") (class "Default")
      (node (ref "D2") (pin "A") (pinfunction "A_A") (pintype "passive"))
      (node (ref "R45") (pin "2") (pinfunction "2_2") (pintype "passive"))
      (node (ref "U$8") (pin "I_SENSE") (pinfunction "I_SENSE_I_SENSE") (pintype "bidirectional"))
    )
    (net (code "9") (name "Net-(C11-Pad1)") (class "Default")
      (node (ref "C11") (pin "1") (pinfunction "1_1") (pintype "passive"))
      (node (ref "SJ4") (pin "2") (pinfunction "2_2") (pintype "passive"))
    )
    (net (code "10") (name "Net-(C17-Pad2)") (class "Default")
      (node (ref "C17") (pin "2") (pinfunction "2_2") (pintype "passive"))
      (node (ref "R21") (pin "1") (pinfunction "1_1") (pintype "passive"))
    )
    (net (code "11") (name "Net-(C18-Pad1)") (class "Default")
      (node (ref "C18") (pin "1") (pinfunction "1_1") (pintype "passive"))
      (node (ref "R24") (pin "1") (pinfunction "1_1") (pintype "passive"))
      (node (ref "X2") (pin "D+") (pinfunction "D+_D+") (pintype "bidirectional"))
    )
    (net (code "12") (name "Net-(C19-Pad1)") (class "Default")
      (node (ref "C19") (pin "1") (pinfunction "1_1") (pintype "passive"))
      (node (ref "R23") (pin "1") (pinfunction "1_1") (pintype "passive"))
      (node (ref "X2") (pin "D-") (pinfunction "D-_D-") (pintype "bidirectional"))
    )
    (net (code "13") (name "Net-(F1-Pad1)") (class "Default")
      (node (ref "F1") (pin "1") (pinfunction "1_1") (pintype "bidirectional"))
      (node (ref "X2") (pin "VBUS") (pinfunction "VBUS_VBUS") (pintype "bidirectional"))
    )
    (net (code "14") (name "Net-(IC1A--IN)") (class "Default")
      (node (ref "IC1") (pin "2") (pinfunction "-IN_2") (pintype "input"))
      (node (ref "R2") (pin "1") (pinfunction "1_1") (pintype "passive"))
      (node (ref "R3") (pin "2") (pinfunction "2_2") (pintype "passive"))
    )
    (net (code "15") (name "Net-(IC1A-OUT)") (class "Default")
      (node (ref "IC1") (pin "1") (pinfunction "OUT_1") (pintype "output"))
      (node (ref "R1") (pin "1") (pinfunction "1_1") (pintype "passive"))
      (node (ref "R2") (pin "2") (pinfunction "2_2") (pintype "passive"))
    )
    (net (code "16") (name "Net-(IC1B--IN)") (class "Default")
      (node (ref "IC1") (pin "6") (pinfunction "-IN_6") (pintype "input"))
      (node (ref "R4") (pin "1") (pinfunction "1_1") (pintype "passive"))
      (node (ref "R6") (pin "2") (pinfunction "2_2") (pintype "passive"))
    )
    (net (code "17") (name "Net-(IC1B-OUT)") (class "Default")
      (node (ref "IC1") (pin "7") (pinfunction "OUT_7") (pintype "output"))
      (node (ref "R4") (pin "2") (pinfunction "2_2") (pintype "passive"))
      (node (ref "R5") (pin "1") (pinfunction "1_1") (pintype "passive"))
    )
    (net (code "18") (name "Net-(IC2A--IN)") (class "Default")
      (node (ref "IC2") (pin "2") (pinfunction "-IN_2") (pintype "input"))
      (node (ref "R13") (pin "1") (pinfunction "1_1") (pintype "passive"))
      (node (ref "R21") (pin "2") (pinfunction "2_2") (pintype "passive"))
      (node (ref "R22") (pin "2") (pinfunction "2_2") (pintype "passive"))
    )
    (net (code "19") (name "Net-(IC2A-OUT)") (class "Default")
      (node (ref "IC2") (pin "1") (pinfunction "OUT_1") (pintype "output"))
      (node (ref "R12") (pin "1") (pinfunction "1_1") (pintype "passive"))
      (node (ref "R13") (pin "2") (pinfunction "2_2") (pintype "passive"))
    )
    (net (code "20") (name "Net-(IC2B-+IN)") (class "Default")
      (node (ref "IC2") (pin "5") (pinfunction "+IN_5") (pintype "input"))
      (node (ref "R10") (pin "2") (pinfunction "2_2") (pintype "passive"))
      (node (ref "R11") (pin "2") (pinfunction "2_2") (pintype "passive"))
    )
    (net (code "21") (name "Net-(IC2B--IN)") (class "Default")
      (node (ref "IC2") (pin "6") (pinfunction "-IN_6") (pintype "input"))
      (node (ref "R8") (pin "1") (pinfunction "1_1") (pintype "passive"))
      (node (ref "R9") (pin "2") (pinfunction "2_2") (pintype "passive"))
    )
    (net (code "22") (name "Net-(IC2B-OUT)") (class "Default")
      (node (ref "C17") (pin "1") (pinfunction "1_1") (pintype "passive"))
      (node (ref "IC2") (pin "7") (pinfunction "OUT_7") (pintype "output"))
      (node (ref "R22") (pin "1") (pinfunction "1_1") (pintype "passive"))
      (node (ref "R8") (pin "2") (pinfunction "2_2") (pintype "passive"))
    )
    (net (code "23") (name "Net-(IC3A-Y)") (class "Default")
      (node (ref "IC3") (pin "5") (pinfunction "Y_5") (pintype "output"))
      (node (ref "R28") (pin "1") (pinfunction "1_1") (pintype "passive"))
    )
    (net (code "24") (name "Net-(IC3A-Z)") (class "Default")
      (node (ref "IC3") (pin "6") (pinfunction "Z_6") (pintype "output"))
      (node (ref "R26") (pin "1") (pinfunction "1_1") (pintype "passive"))
    )
    (net (code "25") (name "Net-(IC4A-Y)") (class "Default")
      (node (ref "IC4") (pin "5") (pinfunction "Y_5") (pintype "output"))
      (node (ref "R31") (pin "1") (pinfunction "1_1") (pintype "passive"))
    )
    (net (code "26") (name "Net-(IC4A-Z)") (class "Default")
      (node (ref "IC4") (pin "6") (pinfunction "Z_6") (pintype "output"))
      (node (ref "R29") (pin "1") (pinfunction "1_1") (pintype "passive"))
    )
    (net (code "27") (name "Net-(IC5-USBDM)") (class "Default")
      (node (ref "IC5") (pin "9") (pinfunction "USBDM_9") (pintype "input"))
      (node (ref "R23") (pin "2") (pinfunction "2_2") (pintype "passive"))
    )
    (net (code "28") (name "Net-(IC5-USBDP)") (class "Default")
      (node (ref "IC5") (pin "8") (pinfunction "USBDP_8") (pintype "input"))
      (node (ref "R24") (pin "2") (pinfunction "2_2") (pintype "passive"))
    )
    (net (code "29") (name "Net-(LED1-PadC)") (class "Default")
      (node (ref "LED1") (pin "C") (pinfunction "C_C") (pintype "passive"))
      (node (ref "R38") (pin "2") (pinfunction "2_2") (pintype "passive"))
    )
    (net (code "30") (name "Net-(LED2-PadC)") (class "Default")
      (node (ref "LED2") (pin "C") (pinfunction "C_C") (pintype "passive"))
      (node (ref "R39") (pin "2") (pinfunction "2_2") (pintype "passive"))
    )
    (net (code "31") (name "Net-(Q1-B)") (class "Default")
      (node (ref "Q1") (pin "1") (pinfunction "B_1") (pintype "passive"))
      (node (ref "R32") (pin "2") (pinfunction "2_2") (pintype "passive"))
    )
    (net (code "32") (name "Net-(Q1-C)") (class "Default")
      (node (ref "Q1") (pin "3") (pinfunction "C_3") (pintype "passive"))
      (node (ref "R25") (pin "1") (pinfunction "1_1") (pintype "passive"))
    )
    (net (code "33") (name "Net-(U$1-C1+)") (class "Default")
      (node (ref "C5") (pin "1") (pinfunction "1_1") (pintype "passive"))
      (node (ref "U$1") (pin "5") (pinfunction "C1+_5") (pintype "bidirectional"))
    )
    (net (code "34") (name "Net-(U$1-C1-)") (class "Default")
      (node (ref "C5") (pin "2") (pinfunction "2_2") (pintype "passive"))
      (node (ref "U$1") (pin "6") (pinfunction "C1-_6") (pintype "bidirectional"))
    )
    (net (code "35") (name "Net-(U$2-C1+)") (class "Default")
      (node (ref "C9") (pin "1") (pinfunction "1_1") (pintype "passive"))
      (node (ref "U$2") (pin "5") (pinfunction "C1+_5") (pintype "bidirectional"))
    )
    (net (code "36") (name "Net-(U$2-C1-)") (class "Default")
      (node (ref "C9") (pin "2") (pinfunction "2_2") (pintype "passive"))
      (node (ref "U$2") (pin "6") (pinfunction "C1-_6") (pintype "bidirectional"))
    )
    (net (code "37") (name "Net-(U$3-G)") (class "Default")
      (node (ref "D1") (pin "A") (pinfunction "A_A") (pintype "passive"))
      (node (ref "R25") (pin "2") (pinfunction "2_2") (pintype "passive"))
      (node (ref "R33") (pin "1") (pinfunction "1_1") (pintype "passive"))
      (node (ref "U$3") (pin "4") (pinfunction "G_4") (pintype "bidirectional"))
      (node (ref "U$6") (pin "4") (pinfunction "G_4") (pintype "bidirectional"))
    )
    (net (code "38") (name "Net-(U4-OUT)") (class "Default")
      (node (ref "C25") (pin "1") (pinfunction "1_1") (pintype "passive"))
      (node (ref "R44") (pin "1") (pinfunction "1_1") (pintype "passive"))
      (node (ref "R45") (pin "1") (pinfunction "1_1") (pintype "passive"))
      (node (ref "U4") (pin "1") (pinfunction "OUT_1") (pintype "bidirectional"))
    )
    (net (code "39") (name "ROV-ALT-VIN") (class "Default")
      (node (ref "JP10") (pin "1") (pinfunction "1_1") (pintype "passive"))
      (node (ref "SJ1") (pin "1") (pinfunction "1_1") (pintype "passive"))
    )
    (net (code "40") (name "ROV-BATT") (class "Default")
      (node (ref "D1") (pin "C") (pinfunction "C_C") (pintype "passive"))
      (node (ref "R33") (pin "2") (pinfunction "2_2") (pintype "passive"))
      (node (ref "SJ2") (pin "1") (pinfunction "1_1") (pintype "passive"))
      (node (ref "U$10") (pin "2A") (pinfunction "2_2A") (pintype "bidirectional"))
      (node (ref "U$10") (pin "2B") (pinfunction "2_2B") (pintype "bidirectional"))
      (node (ref "U$3") (pin "1") (pinfunction "S_1") (pintype "bidirectional"))
      (node (ref "U$3") (pin "2") (pinfunction "S_2") (pintype "bidirectional"))
      (node (ref "U$3") (pin "3") (pinfunction "S_3") (pintype "bidirectional"))
      (node (ref "U$6") (pin "1") (pinfunction "S_1") (pintype "bidirectional"))
      (node (ref "U$6") (pin "2") (pinfunction "S_2") (pintype "bidirectional"))
      (node (ref "U$6") (pin "3") (pinfunction "S_3") (pintype "bidirectional"))
    )
    (net (code "41") (name "ROV-ON") (class "Default")
      (node (ref "JP2") (pin "7") (pinfunction "7_7") (pintype "passive"))
      (node (ref "SJ2") (pin "3") (pinfunction "3_3") (pintype "passive"))
    )
    (net (code "42") (name "ROV-ON-CTRL") (class "Default")
      (node (ref "C11") (pin "2") (pinfunction "2_2") (pintype "passive"))
      (node (ref "JP7") (pin "7") (pinfunction "7_7") (pintype "passive"))
      (node (ref "R17") (pin "1") (pinfunction "1_1") (pintype "passive"))
    )
    (net (code "43") (name "ROV-ON-SELECT") (class "Default")
      (node (ref "R32") (pin "1") (pinfunction "1_1") (pintype "passive"))
      (node (ref "R35") (pin "2") (pinfunction "2_2") (pintype "passive"))
      (node (ref "SJ2") (pin "2") (pinfunction "2_2") (pintype "passive"))
    )
    (net (code "44") (name "ROV-RX") (class "Default")
      (node (ref "IC4") (pin "2") (pinfunction "RO_2") (pintype "output"))
      (node (ref "U$8") (pin "RX") (pinfunction "RX_RX") (pintype "bidirectional"))
    )
    (net (code "45") (name "ROV-TP1+") (class "Default")
      (node (ref "JP2") (pin "1") (pinfunction "1_1") (pintype "passive"))
      (node (ref "R1") (pin "2") (pinfunction "2_2") (pintype "passive"))
    )
    (net (code "46") (name "ROV-TP1-") (class "Default")
      (node (ref "JP2") (pin "2") (pinfunction "2_2") (pintype "passive"))
      (node (ref "R5") (pin "2") (pinfunction "2_2") (pintype "passive"))
    )
    (net (code "47") (name "ROV-TP2+") (class "Default")
      (node (ref "JP2") (pin "3") (pinfunction "3_3") (pintype "passive"))
      (node (ref "R31") (pin "2") (pinfunction "2_2") (pintype "passive"))
    )
    (net (code "48") (name "ROV-TP2-") (class "Default")
      (node (ref "JP2") (pin "4") (pinfunction "4_4") (pintype "passive"))
      (node (ref "R29") (pin "2") (pinfunction "2_2") (pintype "passive"))
    )
    (net (code "49") (name "ROV-TP3+") (class "Default")
      (node (ref "IC4") (pin "8") (pinfunction "A_8") (pintype "input"))
      (node (ref "JP2") (pin "5") (pinfunction "5_5") (pintype "passive"))
      (node (ref "R16") (pin "2") (pinfunction "2_2") (pintype "passive"))
    )
    (net (code "50") (name "ROV-TP3-") (class "Default")
      (node (ref "IC4") (pin "7") (pinfunction "B_7") (pintype "input"))
      (node (ref "JP2") (pin "6") (pinfunction "6_6") (pintype "passive"))
      (node (ref "R16") (pin "1") (pinfunction "1_1") (pintype "passive"))
    )
    (net (code "51") (name "ROV-TX") (class "Default")
      (node (ref "IC4") (pin "3") (pinfunction "DI_3") (pintype "input"))
      (node (ref "U$8") (pin "TX") (pinfunction "TX_TX") (pintype "bidirectional"))
    )
    (net (code "52") (name "ROV-VIN") (class "Default")
      (node (ref "C8") (pin "1") (pinfunction "1_1") (pintype "passive"))
      (node (ref "SJ1") (pin "2") (pinfunction "2_2") (pintype "passive"))
      (node (ref "U$8") (pin "VBAT") (pinfunction "VBAT_VBAT") (pintype "bidirectional"))
      (node (ref "U1") (pin "1") (pinfunction "IN_1") (pintype "input"))
      (node (ref "U5") (pin "1") (pinfunction "IN_1") (pintype "input"))
    )
    (net (code "53") (name "ROV-VIN-PRESENSE") (class "Default")
      (node (ref "R34") (pin "2") (pinfunction "2_2") (pintype "passive"))
      (node (ref "U$3") (pin "5") (pinfunction "D_5") (pintype "bidirectional"))
      (node (ref "U$3") (pin "6") (pinfunction "D_6") (pintype "bidirectional"))
      (node (ref "U$3") (pin "7") (pinfunction "D_7") (pintype "bidirectional"))
      (node (ref "U$3") (pin "8") (pinfunction "D_8") (pintype "bidirectional"))
      (node (ref "U$6") (pin "5") (pinfunction "D_5") (pintype "bidirectional"))
      (node (ref "U$6") (pin "6") (pinfunction "D_6") (pintype "bidirectional"))
      (node (ref "U$6") (pin "7") (pinfunction "D_7") (pintype "bidirectional"))
      (node (ref "U$6") (pin "8") (pinfunction "D_8") (pintype "bidirectional"))
      (node (ref "U4") (pin "3") (pinfunction "VIN+_3") (pintype "bidirectional"))
    )
    (net (code "54") (name "ROV-VIN-SWITCHED") (class "Default")
      (node (ref "R34") (pin "1") (pinfunction "1_1") (pintype "passive"))
      (node (ref "R36") (pin "2") (pinfunction "2_2") (pintype "passive"))
      (node (ref "SJ1") (pin "3") (pinfunction "3_3") (pintype "passive"))
      (node (ref "U$11") (pin "1A") (pinfunction "1_1A") (pintype "bidirectional"))
      (node (ref "U$11") (pin "1B") (pinfunction "1_1B") (pintype "bidirectional"))
      (node (ref "U4") (pin "4") (pinfunction "VIN-_4") (pintype "bidirectional"))
    )
    (net (code "55") (name "RTS") (class "Default")
      (node (ref "IC5") (pin "2") (pinfunction "~{RTS}_2") (pintype "output"))
      (node (ref "SJ4") (pin "1") (pinfunction "1_1") (pintype "passive"))
    )
    (net (code "56") (name "RX-I") (class "Default")
      (node (ref "IC3") (pin "2") (pinfunction "RO_2") (pintype "output"))
      (node (ref "IC5") (pin "4") (pinfunction "RXD_4") (pintype "input"))
      (node (ref "JP15") (pin "2") (pinfunction "2_2") (pintype "passive"))
    )
    (net (code "57") (name "TOP-TP1+") (class "Default")
      (node (ref "JP7") (pin "1") (pinfunction "1_1") (pintype "passive"))
      (node (ref "R14") (pin "2") (pinfunction "2_2") (pintype "passive"))
      (node (ref "R9") (pin "1") (pinfunction "1_1") (pintype "passive"))
    )
    (net (code "58") (name "TOP-TP1-") (class "Default")
      (node (ref "JP7") (pin "2") (pinfunction "2_2") (pintype "passive"))
      (node (ref "R10") (pin "1") (pinfunction "1_1") (pintype "passive"))
      (node (ref "R14") (pin "1") (pinfunction "1_1") (pintype "passive"))
    )
    (net (code "59") (name "TOP-TP2+") (class "Default")
      (node (ref "IC3") (pin "8") (pinfunction "A_8") (pintype "input"))
      (node (ref "JP7") (pin "3") (pinfunction "3_3") (pintype "passive"))
      (node (ref "R15") (pin "2") (pinfunction "2_2") (pintype "passive"))
    )
    (net (code "60") (name "TOP-TP2-") (class "Default")
      (node (ref "IC3") (pin "7") (pinfunction "B_7") (pintype "input"))
      (node (ref "JP7") (pin "4") (pinfunction "4_4") (pintype "passive"))
      (node (ref "R15") (pin "1") (pinfunction "1_1") (pintype "passive"))
    )
    (net (code "61") (name "TOP-TP3+") (class "Default")
      (node (ref "JP7") (pin "5") (pinfunction "5_5") (pintype "passive"))
      (node (ref "R28") (pin "2") (pinfunction "2_2") (pintype "passive"))
    )
    (net (code "62") (name "TOP-TP3-") (class "Default")
      (node (ref "JP7") (pin "6") (pinfunction "6_6") (pintype "passive"))
      (node (ref "R26") (pin "2") (pinfunction "2_2") (pintype "passive"))
    )
    (net (code "63") (name "TOP-VIN") (class "Default")
      (node (ref "C15") (pin "1") (pinfunction "1_1") (pintype "passive"))
      (node (ref "JP9") (pin "1") (pinfunction "1_1") (pintype "passive"))
      (node (ref "U$12") (pin "2A") (pinfunction "2_2A") (pintype "bidirectional"))
      (node (ref "U$12") (pin "2B") (pinfunction "2_2B") (pintype "bidirectional"))
      (node (ref "U2") (pin "1") (pinfunction "IN_1") (pintype "input"))
    )
    (net (code "64") (name "TX-O") (class "Default")
      (node (ref "IC3") (pin "3") (pinfunction "DI_3") (pintype "input"))
      (node (ref "IC5") (pin "1") (pinfunction "TXD_1") (pintype "output"))
      (node (ref "JP15") (pin "1") (pinfunction "1_1") (pintype "passive"))
    )
    (net (code "65") (name "VCC") (class "Default")
      (node (ref "C14") (pin "1") (pinfunction "1_1") (pintype "passive"))
      (node (ref "C16") (pin "A") (pinfunction "+_A") (pintype "passive"))
      (node (ref "C20") (pin "1") (pinfunction "1_1") (pintype "passive"))
      (node (ref "C21") (pin "1") (pinfunction "1_1") (pintype "passive"))
      (node (ref "C3") (pin "1") (pinfunction "1_1") (pintype "passive"))
      (node (ref "F1") (pin "2") (pinfunction "2_2") (pintype "bidirectional"))
      (node (ref "IC2") (pin "8") (pinfunction "V+_8") (pintype "power_in"))
      (node (ref "IC3") (pin "1") (pinfunction "VCC_1") (pintype "power_in"))
      (node (ref "IC5") (pin "12") (pinfunction "VCC_12") (pintype "power_in"))
      (node (ref "JP15") (pin "3") (pinfunction "3_3") (pintype "passive"))
      (node (ref "JP4") (pin "1") (pinfunction "1_1") (pintype "passive"))
      (node (ref "LED2") (pin "A") (pinfunction "A_A") (pintype "passive"))
      (node (ref "R17") (pin "2") (pinfunction "2_2") (pintype "passive"))
      (node (ref "U$2") (pin "3") (pinfunction "VIN_3") (pintype "bidirectional"))
      (node (ref "U$2") (pin "4") (pinfunction "EN_4") (pintype "bidirectional"))
      (node (ref "U2") (pin "3") (pinfunction "OUT_3") (pintype "output"))
    )
    (net (code "66") (name "VCC-ISO") (class "Default")
      (node (ref "C1") (pin "1") (pinfunction "1_1") (pintype "passive"))
      (node (ref "C10") (pin "A") (pinfunction "+_A") (pintype "passive"))
      (node (ref "C22") (pin "1") (pinfunction "1_1") (pintype "passive"))
      (node (ref "C24") (pin "1") (pinfunction "1_1") (pintype "passive"))
      (node (ref "C7") (pin "1") (pinfunction "1_1") (pintype "passive"))
      (node (ref "D2") (pin "C") (pinfunction "C_C") (pintype "passive"))
      (node (ref "IC1") (pin "8") (pinfunction "V+_8") (pintype "power_in"))
      (node (ref "IC4") (pin "1") (pinfunction "VCC_1") (pintype "power_in"))
      (node (ref "LED1") (pin "A") (pinfunction "A_A") (pintype "passive"))
      (node (ref "U$1") (pin "3") (pinfunction "VIN_3") (pintype "bidirectional"))
      (node (ref "U$1") (pin "4") (pinfunction "EN_4") (pintype "bidirectional"))
      (node (ref "U$8") (pin "5V") (pinfunction "5V_5V") (pintype "bidirectional"))
      (node (ref "U4") (pin "5") (pinfunction "V+_5") (pintype "bidirectional"))
      (node (ref "U5") (pin "3") (pinfunction "OUT_3") (pintype "output"))
    )
    (net (code "67") (name "VIDEO-OUT") (class "Default")
      (node (ref "JP6") (pin "PIN") (pinfunction "PIN_PIN") (pintype "bidirectional"))
      (node (ref "R12") (pin "2") (pinfunction "2_2") (pintype "passive"))
    )
    (net (code "68") (name "V_SENSE") (class "Default")
      (node (ref "R36") (pin "1") (pinfunction "1_1") (pintype "passive"))
      (node (ref "R37") (pin "2") (pinfunction "2_2") (pintype "passive"))
      (node (ref "U$8") (pin "V_SENSE") (pinfunction "V_SENSE_V_SENSE") (pintype "bidirectional"))
    )
    (net (code "69") (name "unconnected-(IC5-CBUS0-Pad15)") (class "Default")
      (node (ref "IC5") (pin "15") (pinfunction "CBUS0_15") (pintype "bidirectional"))
    )
    (net (code "70") (name "unconnected-(IC5-CBUS1-Pad14)") (class "Default")
      (node (ref "IC5") (pin "14") (pinfunction "CBUS1_14") (pintype "bidirectional"))
    )
    (net (code "71") (name "unconnected-(IC5-CBUS2-Pad7)") (class "Default")
      (node (ref "IC5") (pin "7") (pinfunction "CBUS2_7") (pintype "bidirectional"))
    )
    (net (code "72") (name "unconnected-(IC5-CBUS3-Pad16)") (class "Default")
      (node (ref "IC5") (pin "16") (pinfunction "CBUS3_16") (pintype "bidirectional"))
    )
    (net (code "73") (name "unconnected-(IC5-~{CTS}-Pad6)") (class "Default")
      (node (ref "IC5") (pin "6") (pinfunction "~{CTS}_6") (pintype "input"))
    )
    (net (code "74") (name "unconnected-(JP1-PadSWITCH)") (class "Default")
      (node (ref "JP1") (pin "SWITCH") (pinfunction "SWITCH_SWITCH") (pintype "bidirectional"))
    )
    (net (code "75") (name "unconnected-(JP6-PadSWITCH)") (class "Default")
      (node (ref "JP6") (pin "SWITCH") (pinfunction "SWITCH_SWITCH") (pintype "bidirectional"))
    )
  )
)
